# easy_bee_Itsybitsy.net
KiCad netlist of a schematic drawn in EAGLE
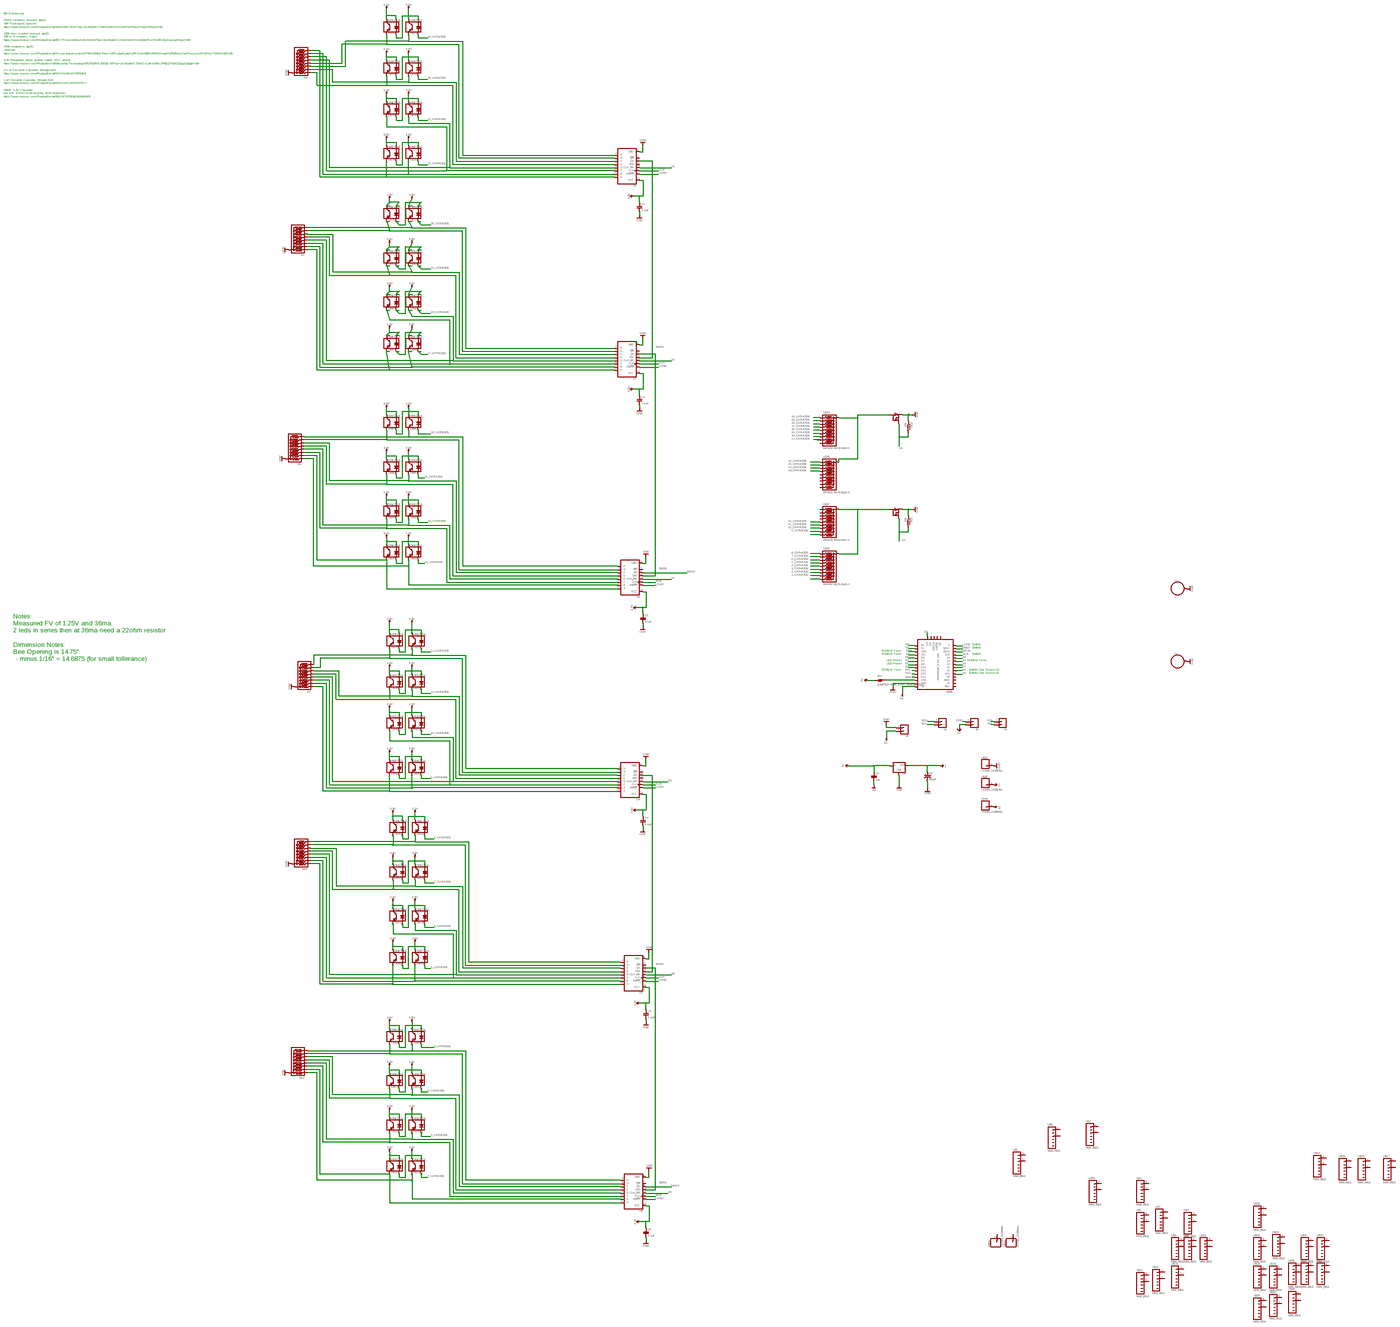
[diagram p0: schematic, sheet 1, overview]
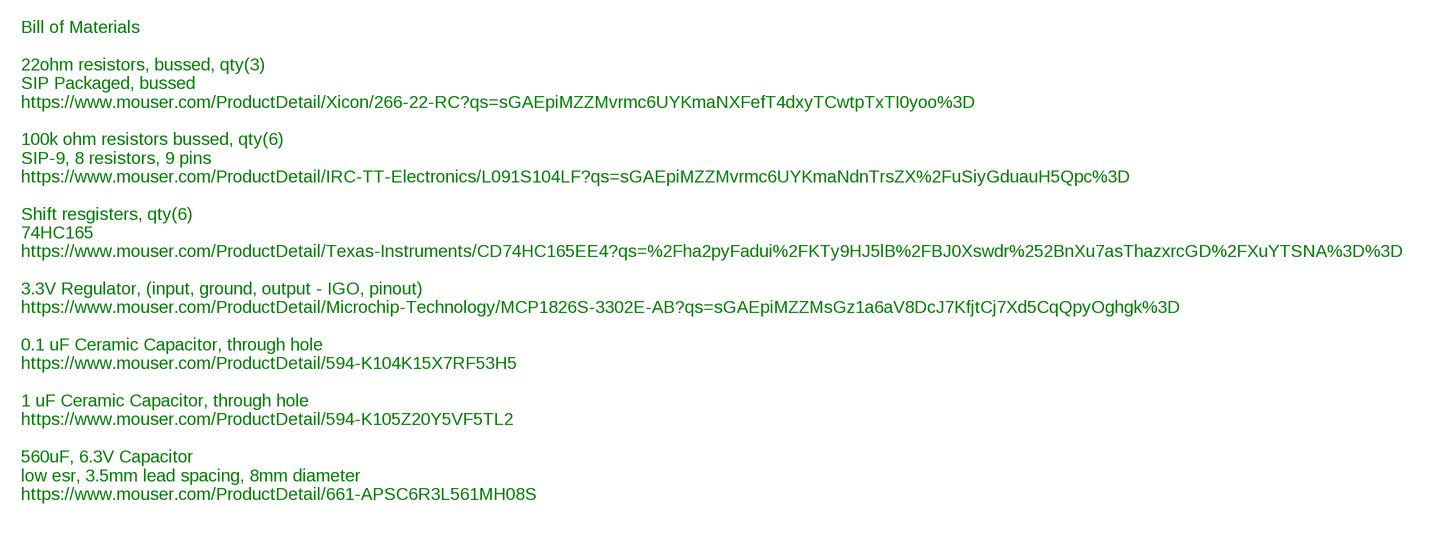
[diagram p1: schematic, sheet 1, part 1 of 5]
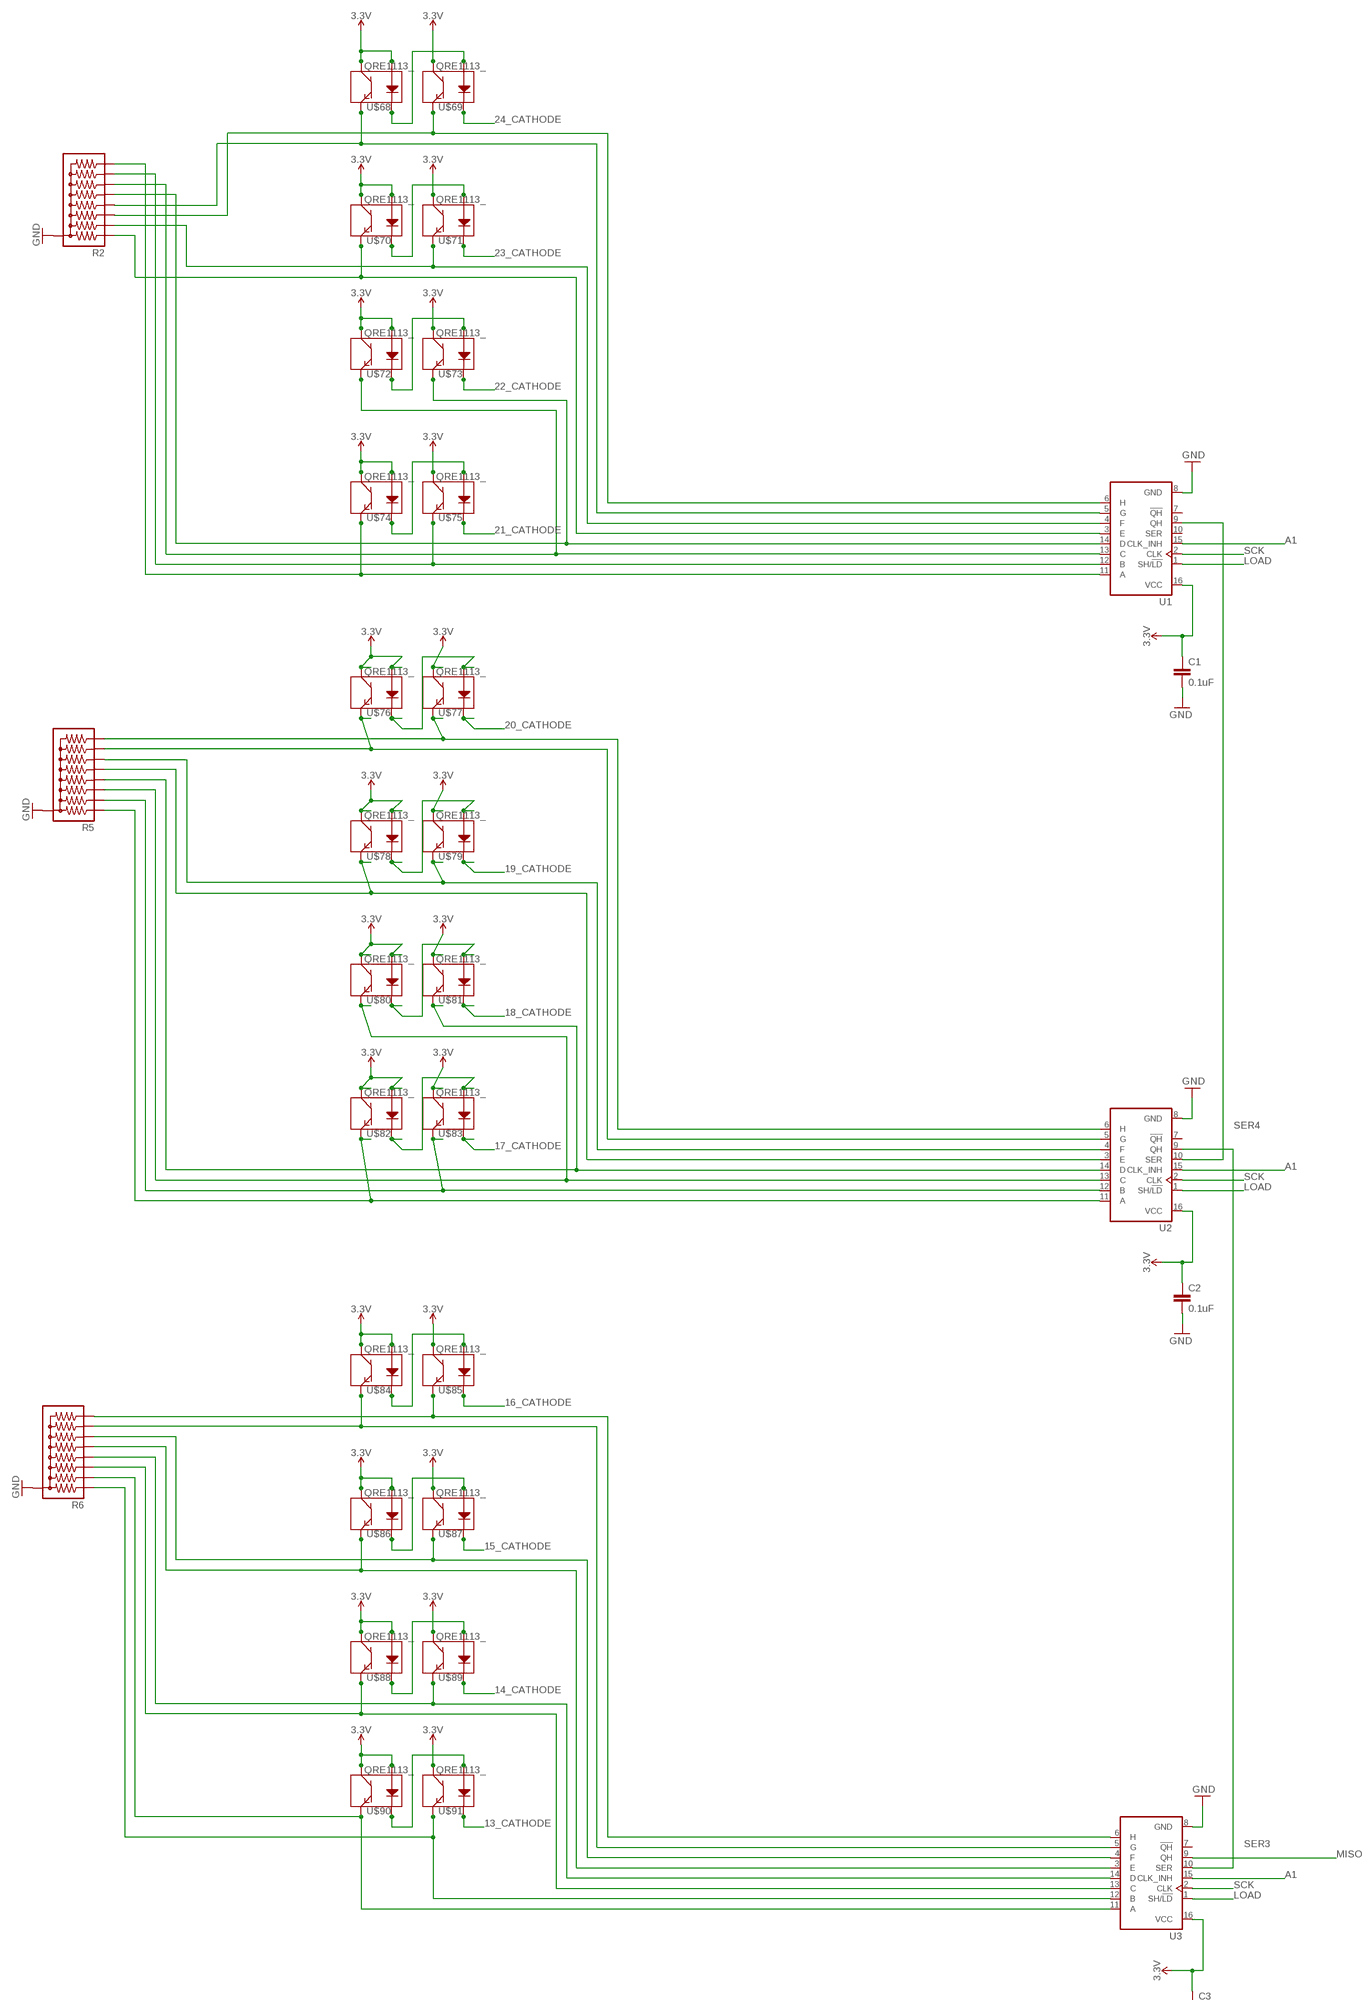
[diagram p2: schematic, sheet 1, part 2 of 5]
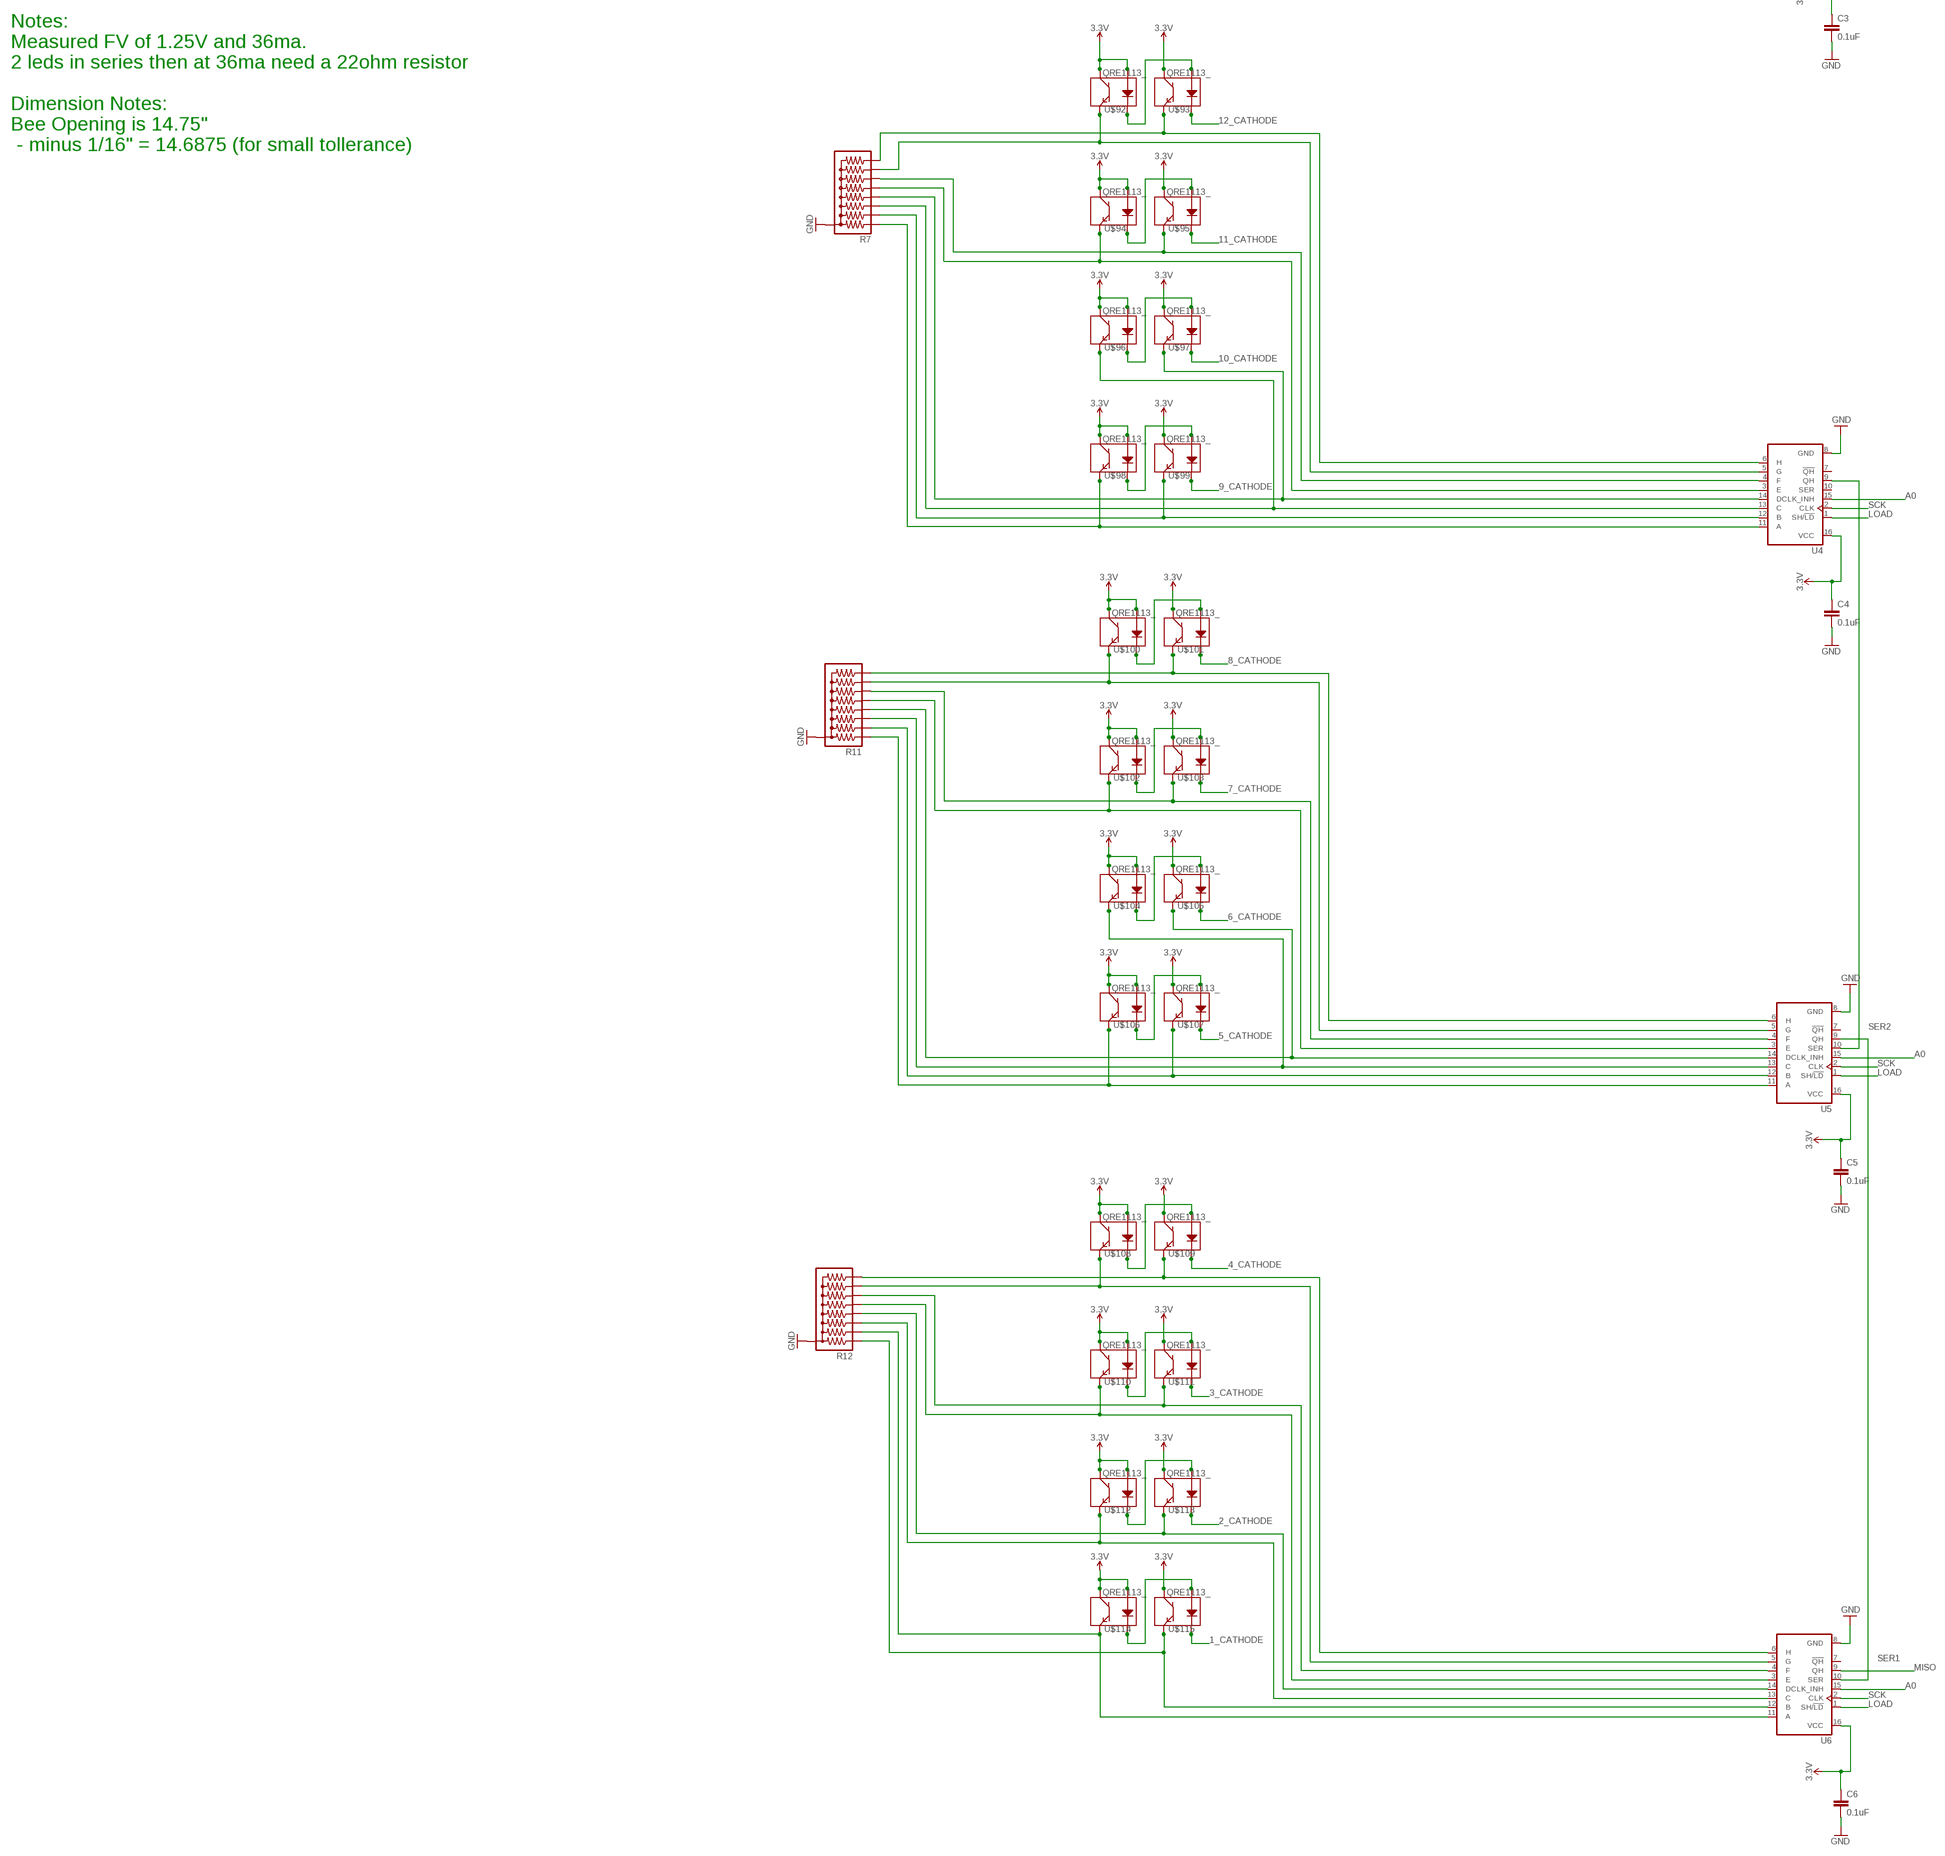
[diagram p3: schematic, sheet 1, part 3 of 5]
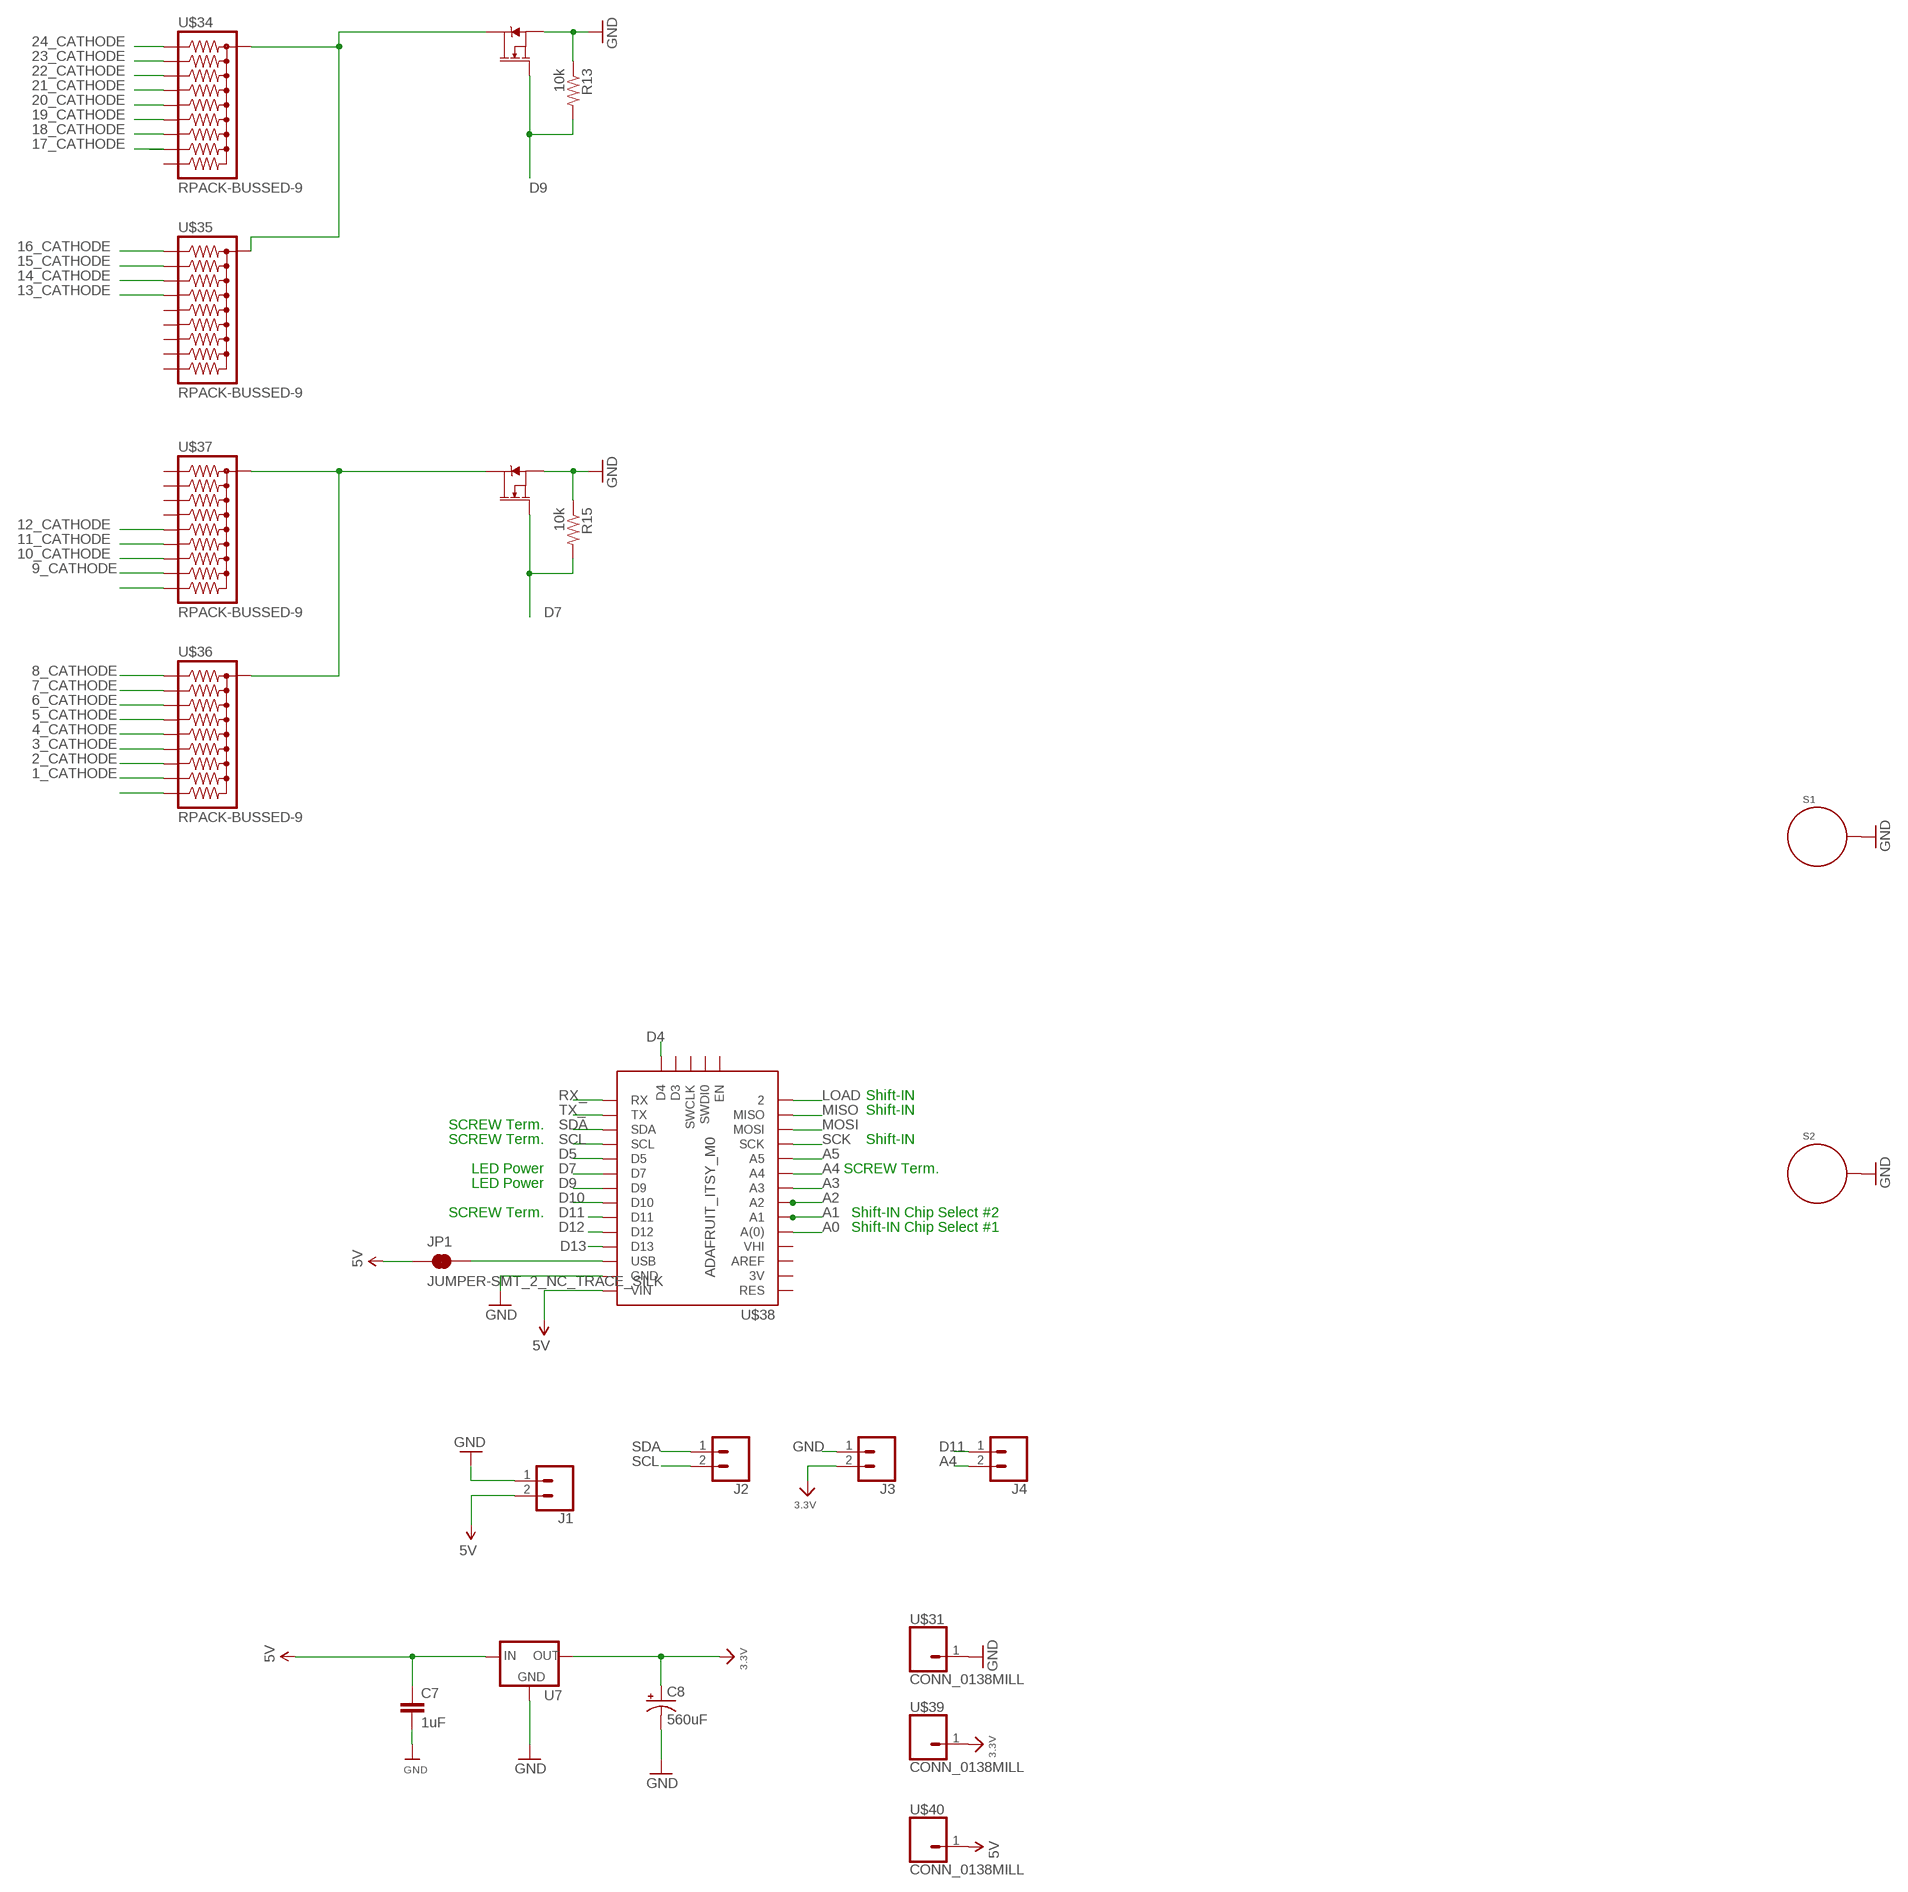
[diagram p4: schematic, sheet 1, part 4 of 5]
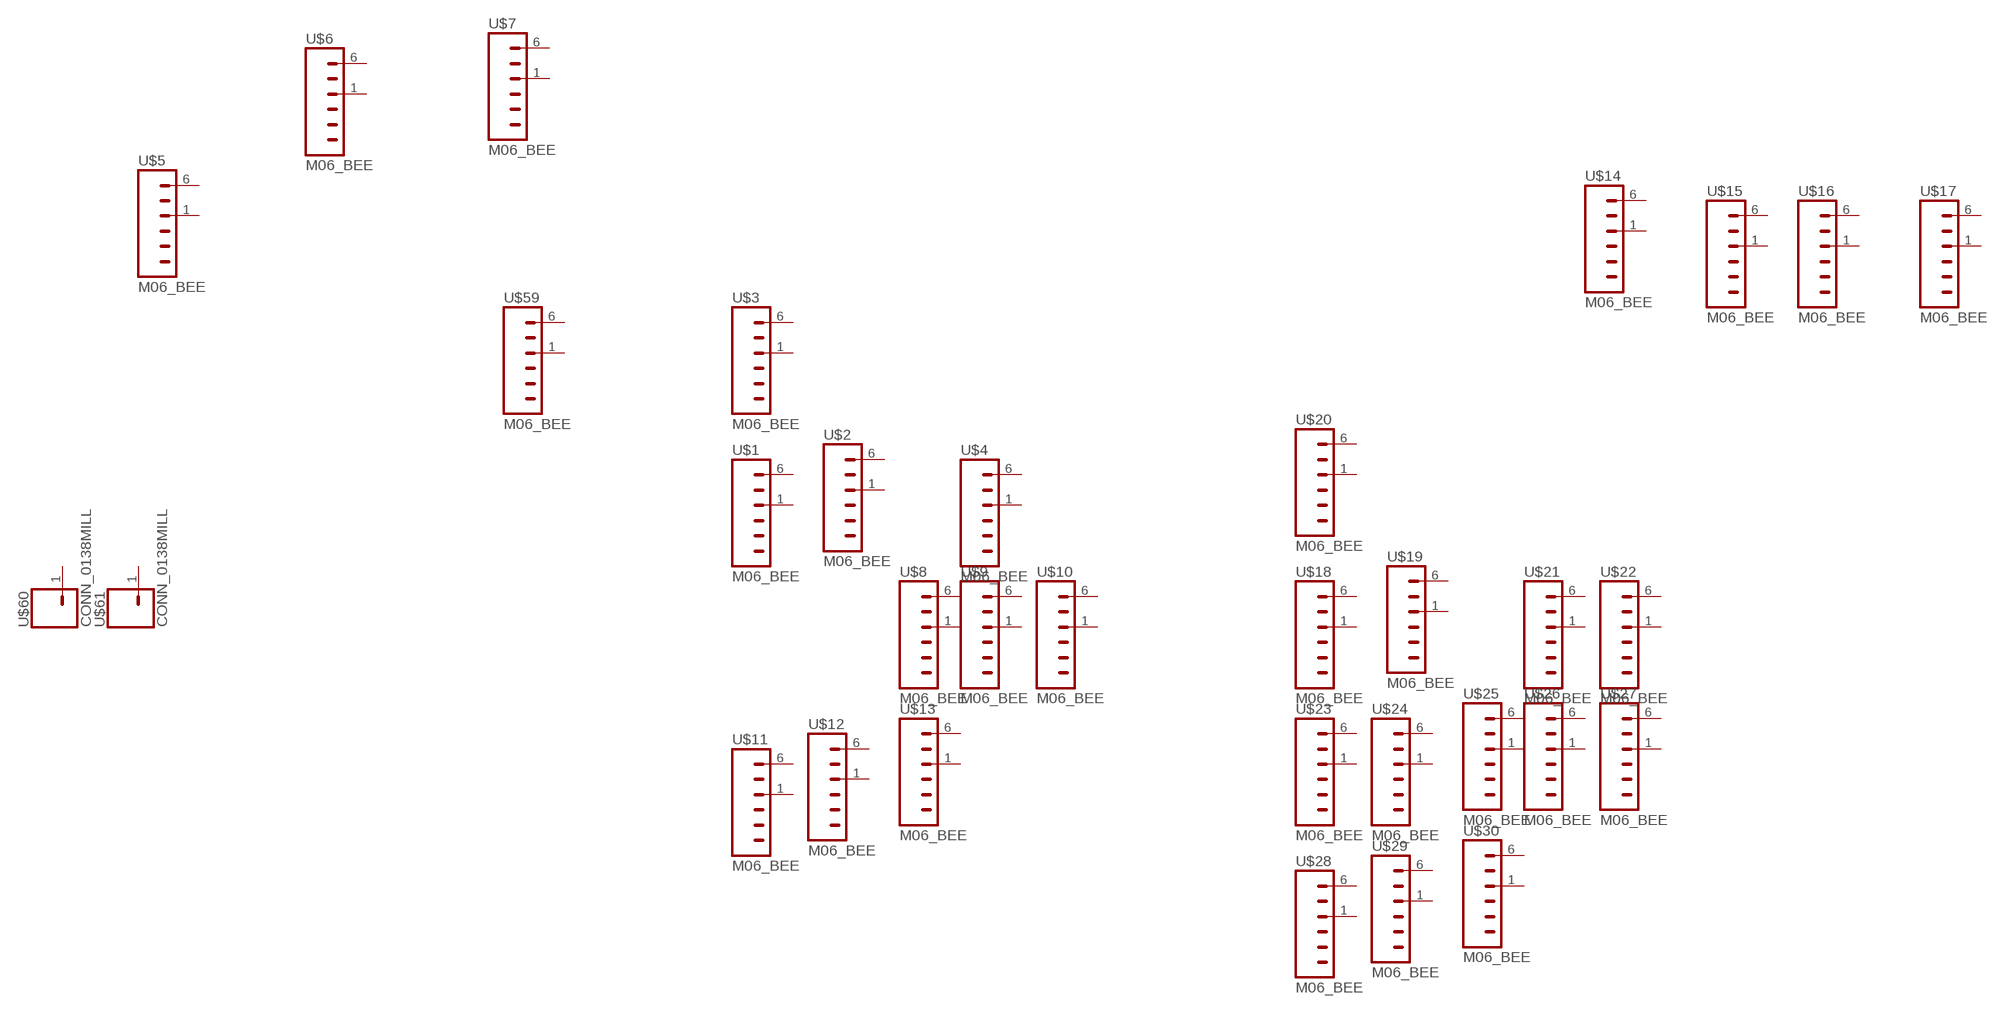
[diagram p5: schematic, sheet 1, part 5 of 5]

(export (version "E")
  (design (tool "Eeschema 10.0.6"))
  (components
    (comp (ref "C1")
      (value "0.1uF")
      (footprint "eagle-import:CAP-PTH-SMALL-KIT")
      (libsource (lib "eagle-import") (part "0.1UF-KIT-EZ-50V-20%"))
    )
    (comp (ref "C2")
      (value "0.1uF")
      (footprint "eagle-import:CAP-PTH-SMALL-KIT")
      (libsource (lib "eagle-import") (part "0.1UF-KIT-EZ-50V-20%"))
    )
    (comp (ref "C3")
      (value "0.1uF")
      (footprint "eagle-import:CAP-PTH-SMALL-KIT")
      (libsource (lib "eagle-import") (part "0.1UF-KIT-EZ-50V-20%"))
    )
    (comp (ref "C4")
      (value "0.1uF")
      (footprint "eagle-import:CAP-PTH-SMALL-KIT")
      (libsource (lib "eagle-import") (part "0.1UF-KIT-EZ-50V-20%"))
    )
    (comp (ref "C5")
      (value "0.1uF")
      (footprint "eagle-import:CAP-PTH-SMALL-KIT")
      (libsource (lib "eagle-import") (part "0.1UF-KIT-EZ-50V-20%"))
    )
    (comp (ref "C6")
      (value "0.1uF")
      (footprint "eagle-import:CAP-PTH-SMALL-KIT")
      (libsource (lib "eagle-import") (part "0.1UF-KIT-EZ-50V-20%"))
    )
    (comp (ref "C7")
      (value "1uF")
      (footprint "eagle-import:CAP-PTH-SMALL-KIT")
      (libsource (lib "eagle-import") (part "0.1UF-KIT-EZ-50V-20%"))
    )
    (comp (ref "C8")
      (value "560uF")
      (footprint "eagle-import:E3,5-8")
      (libsource (lib "eagle-import") (part "CPOL-USE3.5-8"))
    )
    (comp (ref "J1")
      (value "CONN_025MM")
      (footprint "eagle-import:SCREWTERMINAL-5MM-2")
      (libsource (lib "eagle-import") (part "CONN_025MM"))
    )
    (comp (ref "J2")
      (value "CONN_025MM")
      (footprint "eagle-import:SCREWTERMINAL-5MM-2")
      (libsource (lib "eagle-import") (part "CONN_025MM"))
    )
    (comp (ref "J3")
      (value "CONN_025MM")
      (footprint "eagle-import:SCREWTERMINAL-5MM-2")
      (libsource (lib "eagle-import") (part "CONN_025MM"))
    )
    (comp (ref "J4")
      (value "CONN_025MM")
      (footprint "eagle-import:SCREWTERMINAL-5MM-2")
      (libsource (lib "eagle-import") (part "CONN_025MM"))
    )
    (comp (ref "JP1")
      (value "JUMPER-SMT_2_NC_TRACE_SILK")
      (footprint "eagle-import:SMT-JUMPER_2_NC_TRACE_SILK")
      (libsource (lib "eagle-import") (part "JUMPER-SMT_2_NC_TRACE_SILK"))
    )
    (comp (ref "Q6")
      (value "60V/32A/35mΩ")
      (footprint "eagle-import:TO220V")
      (libsource (lib "eagle-import") (part "MOSFET-NCH-FQP30N06L"))
    )
    (comp (ref "Q7")
      (value "60V/32A/35mΩ")
      (footprint "eagle-import:TO220V")
      (libsource (lib "eagle-import") (part "MOSFET-NCH-FQP30N06L"))
    )
    (comp (ref "R2")
      (value "RPACK-BUSSED-8-SIP-PTH-8")
      (footprint "eagle-import:RPACK-SIP-PTH-8")
      (libsource (lib "eagle-import") (part "RPACK-BUSSED-8-SIP-PTH-8"))
    )
    (comp (ref "R5")
      (value "RPACK-BUSSED-8-SIP-PTH-8")
      (footprint "eagle-import:RPACK-SIP-PTH-8")
      (libsource (lib "eagle-import") (part "RPACK-BUSSED-8-SIP-PTH-8"))
    )
    (comp (ref "R6")
      (value "RPACK-BUSSED-8-SIP-PTH-8")
      (footprint "eagle-import:RPACK-SIP-PTH-8")
      (libsource (lib "eagle-import") (part "RPACK-BUSSED-8-SIP-PTH-8"))
    )
    (comp (ref "R7")
      (value "RPACK-BUSSED-8-SIP-PTH-8")
      (footprint "eagle-import:RPACK-SIP-PTH-8")
      (libsource (lib "eagle-import") (part "RPACK-BUSSED-8-SIP-PTH-8"))
    )
    (comp (ref "R11")
      (value "RPACK-BUSSED-8-SIP-PTH-8")
      (footprint "eagle-import:RPACK-SIP-PTH-8")
      (libsource (lib "eagle-import") (part "RPACK-BUSSED-8-SIP-PTH-8"))
    )
    (comp (ref "R12")
      (value "RPACK-BUSSED-8-SIP-PTH-8")
      (footprint "eagle-import:RPACK-SIP-PTH-8")
      (libsource (lib "eagle-import") (part "RPACK-BUSSED-8-SIP-PTH-8"))
    )
    (comp (ref "R13")
      (value "10k")
      (footprint "eagle-import:AXIAL-0.3")
      (libsource (lib "eagle-import") (part "RESISTORAXIAL-0.3"))
    )
    (comp (ref "R15")
      (value "10k")
      (footprint "eagle-import:AXIAL-0.3")
      (libsource (lib "eagle-import") (part "RESISTORAXIAL-0.3"))
    )
    (comp (ref "S1")
      (value "STANDOFF_ELECTRICAL5-32")
      (footprint "eagle-import:STANDOFF_ELECTRICAL_5_32")
      (libsource (lib "eagle-import") (part "STANDOFF_ELECTRICAL5-32"))
    )
    (comp (ref "S2")
      (value "STANDOFF_ELECTRICAL5-32")
      (footprint "eagle-import:STANDOFF_ELECTRICAL_5_32")
      (libsource (lib "eagle-import") (part "STANDOFF_ELECTRICAL5-32"))
    )
    (comp (ref "U$1")
      (value "M06_BEE")
      (footprint "eagle-import:1X06_BEE")
      (libsource (lib "eagle-import") (part "M06_BEE"))
    )
    (comp (ref "U$2")
      (value "M06_BEE")
      (footprint "eagle-import:1X06_BEE")
      (libsource (lib "eagle-import") (part "M06_BEE"))
    )
    (comp (ref "U$3")
      (value "M06_BEE")
      (footprint "eagle-import:1X06_BEE")
      (libsource (lib "eagle-import") (part "M06_BEE"))
    )
    (comp (ref "U$4")
      (value "M06_BEE")
      (footprint "eagle-import:1X06_BEE")
      (libsource (lib "eagle-import") (part "M06_BEE"))
    )
    (comp (ref "U$5")
      (value "M06_BEE")
      (footprint "eagle-import:1X06_BEE")
      (libsource (lib "eagle-import") (part "M06_BEE"))
    )
    (comp (ref "U$6")
      (value "M06_BEE")
      (footprint "eagle-import:1X06_BEE")
      (libsource (lib "eagle-import") (part "M06_BEE"))
    )
    (comp (ref "U$7")
      (value "M06_BEE")
      (footprint "eagle-import:1X06_BEE")
      (libsource (lib "eagle-import") (part "M06_BEE"))
    )
    (comp (ref "U$8")
      (value "M06_BEE")
      (footprint "eagle-import:1X06_BEE")
      (libsource (lib "eagle-import") (part "M06_BEE"))
    )
    (comp (ref "U$9")
      (value "M06_BEE")
      (footprint "eagle-import:1X06_BEE")
      (libsource (lib "eagle-import") (part "M06_BEE"))
    )
    (comp (ref "U$10")
      (value "M06_BEE")
      (footprint "eagle-import:1X06_BEE")
      (libsource (lib "eagle-import") (part "M06_BEE"))
    )
    (comp (ref "U$11")
      (value "M06_BEE")
      (footprint "eagle-import:1X06_BEE")
      (libsource (lib "eagle-import") (part "M06_BEE"))
    )
    (comp (ref "U$12")
      (value "M06_BEE")
      (footprint "eagle-import:1X06_BEE")
      (libsource (lib "eagle-import") (part "M06_BEE"))
    )
    (comp (ref "U$13")
      (value "M06_BEE")
      (footprint "eagle-import:1X06_BEE")
      (libsource (lib "eagle-import") (part "M06_BEE"))
    )
    (comp (ref "U$14")
      (value "M06_BEE")
      (footprint "eagle-import:1X06_BEE")
      (libsource (lib "eagle-import") (part "M06_BEE"))
    )
    (comp (ref "U$15")
      (value "M06_BEE")
      (footprint "eagle-import:1X06_BEE")
      (libsource (lib "eagle-import") (part "M06_BEE"))
    )
    (comp (ref "U$16")
      (value "M06_BEE")
      (footprint "eagle-import:1X06_BEE")
      (libsource (lib "eagle-import") (part "M06_BEE"))
    )
    (comp (ref "U$17")
      (value "M06_BEE")
      (footprint "eagle-import:1X06_BEE")
      (libsource (lib "eagle-import") (part "M06_BEE"))
    )
    (comp (ref "U$18")
      (value "M06_BEE")
      (footprint "eagle-import:1X06_BEE")
      (libsource (lib "eagle-import") (part "M06_BEE"))
    )
    (comp (ref "U$19")
      (value "M06_BEE")
      (footprint "eagle-import:1X06_BEE")
      (libsource (lib "eagle-import") (part "M06_BEE"))
    )
    (comp (ref "U$20")
      (value "M06_BEE")
      (footprint "eagle-import:1X06_BEE")
      (libsource (lib "eagle-import") (part "M06_BEE"))
    )
    (comp (ref "U$21")
      (value "M06_BEE")
      (footprint "eagle-import:1X06_BEE")
      (libsource (lib "eagle-import") (part "M06_BEE"))
    )
    (comp (ref "U$22")
      (value "M06_BEE")
      (footprint "eagle-import:1X06_BEE")
      (libsource (lib "eagle-import") (part "M06_BEE"))
    )
    (comp (ref "U$23")
      (value "M06_BEE")
      (footprint "eagle-import:1X06_BEE")
      (libsource (lib "eagle-import") (part "M06_BEE"))
    )
    (comp (ref "U$24")
      (value "M06_BEE")
      (footprint "eagle-import:1X06_BEE")
      (libsource (lib "eagle-import") (part "M06_BEE"))
    )
    (comp (ref "U$25")
      (value "M06_BEE")
      (footprint "eagle-import:1X06_BEE")
      (libsource (lib "eagle-import") (part "M06_BEE"))
    )
    (comp (ref "U$26")
      (value "M06_BEE")
      (footprint "eagle-import:1X06_BEE")
      (libsource (lib "eagle-import") (part "M06_BEE"))
    )
    (comp (ref "U$27")
      (value "M06_BEE")
      (footprint "eagle-import:1X06_BEE")
      (libsource (lib "eagle-import") (part "M06_BEE"))
    )
    (comp (ref "U$28")
      (value "M06_BEE")
      (footprint "eagle-import:1X06_BEE")
      (libsource (lib "eagle-import") (part "M06_BEE"))
    )
    (comp (ref "U$29")
      (value "M06_BEE")
      (footprint "eagle-import:1X06_BEE")
      (libsource (lib "eagle-import") (part "M06_BEE"))
    )
    (comp (ref "U$30")
      (value "M06_BEE")
      (footprint "eagle-import:1X06_BEE")
      (libsource (lib "eagle-import") (part "M06_BEE"))
    )
    (comp (ref "U$31")
      (value "CONN_0138MILL")
      (footprint "eagle-import:1X01-40MILL")
      (libsource (lib "eagle-import") (part "CONN_0138MILL"))
    )
    (comp (ref "U$34")
      (value "RPACK-BUSSED-9")
      (footprint "eagle-import:RPACK-SIP-PTH-9")
      (libsource (lib "eagle-import") (part "RPACK-BUSSED-9"))
    )
    (comp (ref "U$35")
      (value "RPACK-BUSSED-9")
      (footprint "eagle-import:RPACK-SIP-PTH-9")
      (libsource (lib "eagle-import") (part "RPACK-BUSSED-9"))
    )
    (comp (ref "U$36")
      (value "RPACK-BUSSED-9")
      (footprint "eagle-import:RPACK-SIP-PTH-9")
      (libsource (lib "eagle-import") (part "RPACK-BUSSED-9"))
    )
    (comp (ref "U$37")
      (value "RPACK-BUSSED-9")
      (footprint "eagle-import:RPACK-SIP-PTH-9")
      (libsource (lib "eagle-import") (part "RPACK-BUSSED-9"))
    )
    (comp (ref "U$38")
      (value "ADAFRUIT_ITSY_M0")
      (footprint "eagle-import:ADAFRUIT_ITS_M0")
      (libsource (lib "eagle-import") (part "ADAFRUIT_ITSY_M0"))
    )
    (comp (ref "U$39")
      (value "CONN_0138MILL")
      (footprint "eagle-import:1X01-40MILL")
      (libsource (lib "eagle-import") (part "CONN_0138MILL"))
    )
    (comp (ref "U$40")
      (value "CONN_0138MILL")
      (footprint "eagle-import:1X01-40MILL")
      (libsource (lib "eagle-import") (part "CONN_0138MILL"))
    )
    (comp (ref "U$59")
      (value "M06_BEE")
      (footprint "eagle-import:1X06_BEE")
      (libsource (lib "eagle-import") (part "M06_BEE"))
    )
    (comp (ref "U$60")
      (value "CONN_0138MILL")
      (footprint "eagle-import:1X01-40MILL")
      (libsource (lib "eagle-import") (part "CONN_0138MILL"))
    )
    (comp (ref "U$61")
      (value "CONN_0138MILL")
      (footprint "eagle-import:1X01-40MILL")
      (libsource (lib "eagle-import") (part "CONN_0138MILL"))
    )
    (comp (ref "U$68")
      (value "QRE1113_")
      (footprint "eagle-import:DIP400W50P180L360H200Q4")
      (libsource (lib "eagle-import") (part "QRE1113_"))
    )
    (comp (ref "U$69")
      (value "QRE1113_")
      (footprint "eagle-import:DIP400W50P180L360H200Q4")
      (libsource (lib "eagle-import") (part "QRE1113_"))
    )
    (comp (ref "U$70")
      (value "QRE1113_")
      (footprint "eagle-import:DIP400W50P180L360H200Q4")
      (libsource (lib "eagle-import") (part "QRE1113_"))
    )
    (comp (ref "U$71")
      (value "QRE1113_")
      (footprint "eagle-import:DIP400W50P180L360H200Q4")
      (libsource (lib "eagle-import") (part "QRE1113_"))
    )
    (comp (ref "U$72")
      (value "QRE1113_")
      (footprint "eagle-import:DIP400W50P180L360H200Q4")
      (libsource (lib "eagle-import") (part "QRE1113_"))
    )
    (comp (ref "U$73")
      (value "QRE1113_")
      (footprint "eagle-import:DIP400W50P180L360H200Q4")
      (libsource (lib "eagle-import") (part "QRE1113_"))
    )
    (comp (ref "U$74")
      (value "QRE1113_")
      (footprint "eagle-import:DIP400W50P180L360H200Q4")
      (libsource (lib "eagle-import") (part "QRE1113_"))
    )
    (comp (ref "U$75")
      (value "QRE1113_")
      (footprint "eagle-import:DIP400W50P180L360H200Q4")
      (libsource (lib "eagle-import") (part "QRE1113_"))
    )
    (comp (ref "U$76")
      (value "QRE1113_")
      (footprint "eagle-import:DIP400W50P180L360H200Q4")
      (libsource (lib "eagle-import") (part "QRE1113_"))
    )
    (comp (ref "U$77")
      (value "QRE1113_")
      (footprint "eagle-import:DIP400W50P180L360H200Q4")
      (libsource (lib "eagle-import") (part "QRE1113_"))
    )
    (comp (ref "U$78")
      (value "QRE1113_")
      (footprint "eagle-import:DIP400W50P180L360H200Q4")
      (libsource (lib "eagle-import") (part "QRE1113_"))
    )
    (comp (ref "U$79")
      (value "QRE1113_")
      (footprint "eagle-import:DIP400W50P180L360H200Q4")
      (libsource (lib "eagle-import") (part "QRE1113_"))
    )
    (comp (ref "U$80")
      (value "QRE1113_")
      (footprint "eagle-import:DIP400W50P180L360H200Q4")
      (libsource (lib "eagle-import") (part "QRE1113_"))
    )
    (comp (ref "U$81")
      (value "QRE1113_")
      (footprint "eagle-import:DIP400W50P180L360H200Q4")
      (libsource (lib "eagle-import") (part "QRE1113_"))
    )
    (comp (ref "U$82")
      (value "QRE1113_")
      (footprint "eagle-import:DIP400W50P180L360H200Q4")
      (libsource (lib "eagle-import") (part "QRE1113_"))
    )
    (comp (ref "U$83")
      (value "QRE1113_")
      (footprint "eagle-import:DIP400W50P180L360H200Q4")
      (libsource (lib "eagle-import") (part "QRE1113_"))
    )
    (comp (ref "U$84")
      (value "QRE1113_")
      (footprint "eagle-import:DIP400W50P180L360H200Q4")
      (libsource (lib "eagle-import") (part "QRE1113_"))
    )
    (comp (ref "U$85")
      (value "QRE1113_")
      (footprint "eagle-import:DIP400W50P180L360H200Q4")
      (libsource (lib "eagle-import") (part "QRE1113_"))
    )
    (comp (ref "U$86")
      (value "QRE1113_")
      (footprint "eagle-import:DIP400W50P180L360H200Q4")
      (libsource (lib "eagle-import") (part "QRE1113_"))
    )
    (comp (ref "U$87")
      (value "QRE1113_")
      (footprint "eagle-import:DIP400W50P180L360H200Q4")
      (libsource (lib "eagle-import") (part "QRE1113_"))
    )
    (comp (ref "U$88")
      (value "QRE1113_")
      (footprint "eagle-import:DIP400W50P180L360H200Q4")
      (libsource (lib "eagle-import") (part "QRE1113_"))
    )
    (comp (ref "U$89")
      (value "QRE1113_")
      (footprint "eagle-import:DIP400W50P180L360H200Q4")
      (libsource (lib "eagle-import") (part "QRE1113_"))
    )
    (comp (ref "U$90")
      (value "QRE1113_")
      (footprint "eagle-import:DIP400W50P180L360H200Q4")
      (libsource (lib "eagle-import") (part "QRE1113_"))
    )
    (comp (ref "U$91")
      (value "QRE1113_")
      (footprint "eagle-import:DIP400W50P180L360H200Q4")
      (libsource (lib "eagle-import") (part "QRE1113_"))
    )
    (comp (ref "U$92")
      (value "QRE1113_")
      (footprint "eagle-import:DIP400W50P180L360H200Q4")
      (libsource (lib "eagle-import") (part "QRE1113_"))
    )
    (comp (ref "U$93")
      (value "QRE1113_")
      (footprint "eagle-import:DIP400W50P180L360H200Q4")
      (libsource (lib "eagle-import") (part "QRE1113_"))
    )
    (comp (ref "U$94")
      (value "QRE1113_")
      (footprint "eagle-import:DIP400W50P180L360H200Q4")
      (libsource (lib "eagle-import") (part "QRE1113_"))
    )
    (comp (ref "U$95")
      (value "QRE1113_")
      (footprint "eagle-import:DIP400W50P180L360H200Q4")
      (libsource (lib "eagle-import") (part "QRE1113_"))
    )
    (comp (ref "U$96")
      (value "QRE1113_")
      (footprint "eagle-import:DIP400W50P180L360H200Q4")
      (libsource (lib "eagle-import") (part "QRE1113_"))
    )
    (comp (ref "U$97")
      (value "QRE1113_")
      (footprint "eagle-import:DIP400W50P180L360H200Q4")
      (libsource (lib "eagle-import") (part "QRE1113_"))
    )
    (comp (ref "U$98")
      (value "QRE1113_")
      (footprint "eagle-import:DIP400W50P180L360H200Q4")
      (libsource (lib "eagle-import") (part "QRE1113_"))
    )
    (comp (ref "U$99")
      (value "QRE1113_")
      (footprint "eagle-import:DIP400W50P180L360H200Q4")
      (libsource (lib "eagle-import") (part "QRE1113_"))
    )
    (comp (ref "U$100")
      (value "QRE1113_")
      (footprint "eagle-import:DIP400W50P180L360H200Q4")
      (libsource (lib "eagle-import") (part "QRE1113_"))
    )
    (comp (ref "U$101")
      (value "QRE1113_")
      (footprint "eagle-import:DIP400W50P180L360H200Q4")
      (libsource (lib "eagle-import") (part "QRE1113_"))
    )
    (comp (ref "U$102")
      (value "QRE1113_")
      (footprint "eagle-import:DIP400W50P180L360H200Q4")
      (libsource (lib "eagle-import") (part "QRE1113_"))
    )
    (comp (ref "U$103")
      (value "QRE1113_")
      (footprint "eagle-import:DIP400W50P180L360H200Q4")
      (libsource (lib "eagle-import") (part "QRE1113_"))
    )
    (comp (ref "U$104")
      (value "QRE1113_")
      (footprint "eagle-import:DIP400W50P180L360H200Q4")
      (libsource (lib "eagle-import") (part "QRE1113_"))
    )
    (comp (ref "U$105")
      (value "QRE1113_")
      (footprint "eagle-import:DIP400W50P180L360H200Q4")
      (libsource (lib "eagle-import") (part "QRE1113_"))
    )
    (comp (ref "U$106")
      (value "QRE1113_")
      (footprint "eagle-import:DIP400W50P180L360H200Q4")
      (libsource (lib "eagle-import") (part "QRE1113_"))
    )
    (comp (ref "U$107")
      (value "QRE1113_")
      (footprint "eagle-import:DIP400W50P180L360H200Q4")
      (libsource (lib "eagle-import") (part "QRE1113_"))
    )
    (comp (ref "U$108")
      (value "QRE1113_")
      (footprint "eagle-import:DIP400W50P180L360H200Q4")
      (libsource (lib "eagle-import") (part "QRE1113_"))
    )
    (comp (ref "U$109")
      (value "QRE1113_")
      (footprint "eagle-import:DIP400W50P180L360H200Q4")
      (libsource (lib "eagle-import") (part "QRE1113_"))
    )
    (comp (ref "U$110")
      (value "QRE1113_")
      (footprint "eagle-import:DIP400W50P180L360H200Q4")
      (libsource (lib "eagle-import") (part "QRE1113_"))
    )
    (comp (ref "U$111")
      (value "QRE1113_")
      (footprint "eagle-import:DIP400W50P180L360H200Q4")
      (libsource (lib "eagle-import") (part "QRE1113_"))
    )
    (comp (ref "U$112")
      (value "QRE1113_")
      (footprint "eagle-import:DIP400W50P180L360H200Q4")
      (libsource (lib "eagle-import") (part "QRE1113_"))
    )
    (comp (ref "U$113")
      (value "QRE1113_")
      (footprint "eagle-import:DIP400W50P180L360H200Q4")
      (libsource (lib "eagle-import") (part "QRE1113_"))
    )
    (comp (ref "U$114")
      (value "QRE1113_")
      (footprint "eagle-import:DIP400W50P180L360H200Q4")
      (libsource (lib "eagle-import") (part "QRE1113_"))
    )
    (comp (ref "U$115")
      (value "QRE1113_")
      (footprint "eagle-import:DIP400W50P180L360H200Q4")
      (libsource (lib "eagle-import") (part "QRE1113_"))
    )
    (comp (ref "U1")
      (value "74165")
      (footprint "eagle-import:DIP16")
      (libsource (lib "eagle-import") (part "74165"))
    )
    (comp (ref "U2")
      (value "74165")
      (footprint "eagle-import:DIP16")
      (libsource (lib "eagle-import") (part "74165"))
    )
    (comp (ref "U3")
      (value "74165")
      (footprint "eagle-import:DIP16")
      (libsource (lib "eagle-import") (part "74165"))
    )
    (comp (ref "U4")
      (value "74165")
      (footprint "eagle-import:DIP16")
      (libsource (lib "eagle-import") (part "74165"))
    )
    (comp (ref "U5")
      (value "74165")
      (footprint "eagle-import:DIP16")
      (libsource (lib "eagle-import") (part "74165"))
    )
    (comp (ref "U6")
      (value "74165")
      (footprint "eagle-import:DIP16")
      (libsource (lib "eagle-import") (part "74165"))
    )
    (comp (ref "U7")
      (value "V_REG_78XXSINK")
      (footprint "eagle-import:TO220-IGO")
      (libsource (lib "eagle-import") (part "V_REG_78XXSINK"))
    )
  )
  (nets
    (net (code "1") (name "/1_CATHODE") (class "Default")
      (node (ref "U$115") (pin "2") (pinfunction "K_2") (pintype "bidirectional"))
      (node (ref "U$36") (pin "P$9") (pinfunction "9_P$9") (pintype "passive"))
    )
    (net (code "2") (name "/2_CATHODE") (class "Default")
      (node (ref "U$113") (pin "2") (pinfunction "K_2") (pintype "bidirectional"))
      (node (ref "U$36") (pin "P$8") (pinfunction "8_P$8") (pintype "passive"))
    )
    (net (code "3") (name "/3_CATHODE") (class "Default")
      (node (ref "U$111") (pin "2") (pinfunction "K_2") (pintype "bidirectional"))
      (node (ref "U$36") (pin "P$7") (pinfunction "7_P$7") (pintype "passive"))
    )
    (net (code "4") (name "/4_CATHODE") (class "Default")
      (node (ref "U$109") (pin "2") (pinfunction "K_2") (pintype "bidirectional"))
      (node (ref "U$36") (pin "P$6") (pinfunction "6_P$6") (pintype "passive"))
    )
    (net (code "5") (name "/5_CATHODE") (class "Default")
      (node (ref "U$107") (pin "2") (pinfunction "K_2") (pintype "bidirectional"))
      (node (ref "U$36") (pin "P$5") (pinfunction "5_P$5") (pintype "passive"))
    )
    (net (code "6") (name "/6_CATHODE") (class "Default")
      (node (ref "U$105") (pin "2") (pinfunction "K_2") (pintype "bidirectional"))
      (node (ref "U$36") (pin "P$4") (pinfunction "4_P$4") (pintype "passive"))
    )
    (net (code "7") (name "/7_CATHODE") (class "Default")
      (node (ref "U$103") (pin "2") (pinfunction "K_2") (pintype "bidirectional"))
      (node (ref "U$36") (pin "P$3") (pinfunction "3_P$3") (pintype "passive"))
    )
    (net (code "8") (name "/8_CATHODE") (class "Default")
      (node (ref "U$101") (pin "2") (pinfunction "K_2") (pintype "bidirectional"))
      (node (ref "U$36") (pin "P$2") (pinfunction "2_P$2") (pintype "passive"))
    )
    (net (code "9") (name "/9_CATHODE") (class "Default")
      (node (ref "U$37") (pin "P$9") (pinfunction "9_P$9") (pintype "passive"))
      (node (ref "U$99") (pin "2") (pinfunction "K_2") (pintype "bidirectional"))
    )
    (net (code "10") (name "/10_CATHODE") (class "Default")
      (node (ref "U$37") (pin "P$8") (pinfunction "8_P$8") (pintype "passive"))
      (node (ref "U$97") (pin "2") (pinfunction "K_2") (pintype "bidirectional"))
    )
    (net (code "11") (name "/11_CATHODE") (class "Default")
      (node (ref "U$37") (pin "P$7") (pinfunction "7_P$7") (pintype "passive"))
      (node (ref "U$95") (pin "2") (pinfunction "K_2") (pintype "bidirectional"))
    )
    (net (code "12") (name "/12_CATHODE") (class "Default")
      (node (ref "U$37") (pin "P$6") (pinfunction "6_P$6") (pintype "passive"))
      (node (ref "U$93") (pin "2") (pinfunction "K_2") (pintype "bidirectional"))
    )
    (net (code "13") (name "/13_CATHODE") (class "Default")
      (node (ref "U$35") (pin "P$5") (pinfunction "5_P$5") (pintype "passive"))
      (node (ref "U$91") (pin "2") (pinfunction "K_2") (pintype "bidirectional"))
    )
    (net (code "14") (name "/14_CATHODE") (class "Default")
      (node (ref "U$35") (pin "P$4") (pinfunction "4_P$4") (pintype "passive"))
      (node (ref "U$89") (pin "2") (pinfunction "K_2") (pintype "bidirectional"))
    )
    (net (code "15") (name "/15_CATHODE") (class "Default")
      (node (ref "U$35") (pin "P$3") (pinfunction "3_P$3") (pintype "passive"))
      (node (ref "U$87") (pin "2") (pinfunction "K_2") (pintype "bidirectional"))
    )
    (net (code "16") (name "/16_CATHODE") (class "Default")
      (node (ref "U$35") (pin "P$2") (pinfunction "2_P$2") (pintype "passive"))
      (node (ref "U$85") (pin "2") (pinfunction "K_2") (pintype "bidirectional"))
    )
    (net (code "17") (name "/17_CATHODE") (class "Default")
      (node (ref "U$34") (pin "P$9") (pinfunction "9_P$9") (pintype "passive"))
      (node (ref "U$83") (pin "2") (pinfunction "K_2") (pintype "bidirectional"))
    )
    (net (code "18") (name "/18_CATHODE") (class "Default")
      (node (ref "U$34") (pin "P$8") (pinfunction "8_P$8") (pintype "passive"))
      (node (ref "U$81") (pin "2") (pinfunction "K_2") (pintype "bidirectional"))
    )
    (net (code "19") (name "/19_CATHODE") (class "Default")
      (node (ref "U$34") (pin "P$7") (pinfunction "7_P$7") (pintype "passive"))
      (node (ref "U$79") (pin "2") (pinfunction "K_2") (pintype "bidirectional"))
    )
    (net (code "20") (name "/20_CATHODE") (class "Default")
      (node (ref "U$34") (pin "P$6") (pinfunction "6_P$6") (pintype "passive"))
      (node (ref "U$77") (pin "2") (pinfunction "K_2") (pintype "bidirectional"))
    )
    (net (code "21") (name "/21_CATHODE") (class "Default")
      (node (ref "U$34") (pin "P$5") (pinfunction "5_P$5") (pintype "passive"))
      (node (ref "U$75") (pin "2") (pinfunction "K_2") (pintype "bidirectional"))
    )
    (net (code "22") (name "/22_CATHODE") (class "Default")
      (node (ref "U$34") (pin "P$4") (pinfunction "4_P$4") (pintype "passive"))
      (node (ref "U$73") (pin "2") (pinfunction "K_2") (pintype "bidirectional"))
    )
    (net (code "23") (name "/23_CATHODE") (class "Default")
      (node (ref "U$34") (pin "P$3") (pinfunction "3_P$3") (pintype "passive"))
      (node (ref "U$71") (pin "2") (pinfunction "K_2") (pintype "bidirectional"))
    )
    (net (code "24") (name "/24_CATHODE") (class "Default")
      (node (ref "U$34") (pin "P$2") (pinfunction "2_P$2") (pintype "passive"))
      (node (ref "U$69") (pin "2") (pinfunction "K_2") (pintype "bidirectional"))
    )
    (net (code "25") (name "/A0") (class "Default")
      (node (ref "U$38") (pin "A0") (pinfunction "A(0)_A0") (pintype "bidirectional"))
      (node (ref "U4") (pin "15") (pinfunction "CLK_INH_15") (pintype "input"))
      (node (ref "U5") (pin "15") (pinfunction "CLK_INH_15") (pintype "input"))
      (node (ref "U6") (pin "15") (pinfunction "CLK_INH_15") (pintype "input"))
    )
    (net (code "26") (name "/A1") (class "Default")
      (node (ref "U$38") (pin "A1") (pinfunction "A1_A1") (pintype "bidirectional"))
      (node (ref "U1") (pin "15") (pinfunction "CLK_INH_15") (pintype "input"))
      (node (ref "U2") (pin "15") (pinfunction "CLK_INH_15") (pintype "input"))
      (node (ref "U3") (pin "15") (pinfunction "CLK_INH_15") (pintype "input"))
    )
    (net (code "27") (name "/A2") (class "Default")
      (node (ref "U$38") (pin "A2") (pinfunction "A2_A2") (pintype "bidirectional"))
    )
    (net (code "28") (name "/A3") (class "Default")
      (node (ref "U$38") (pin "A3") (pinfunction "A3_A3") (pintype "bidirectional"))
    )
    (net (code "29") (name "/A4") (class "Default")
      (node (ref "J4") (pin "2") (pinfunction "2_2") (pintype "passive"))
      (node (ref "U$38") (pin "A4") (pinfunction "A4_A4") (pintype "bidirectional"))
    )
    (net (code "30") (name "/A5") (class "Default")
      (node (ref "U$38") (pin "A5") (pinfunction "A5_A5") (pintype "bidirectional"))
    )
    (net (code "31") (name "/D4") (class "Default")
      (node (ref "U$38") (pin "D4") (pinfunction "D4_D4") (pintype "bidirectional"))
    )
    (net (code "32") (name "/D5") (class "Default")
      (node (ref "U$38") (pin "D5") (pinfunction "D5_D5") (pintype "bidirectional"))
    )
    (net (code "33") (name "/D7") (class "Default")
      (node (ref "Q7") (pin "1") (pinfunction "G_1") (pintype "bidirectional"))
      (node (ref "R15") (pin "P$2") (pinfunction "2_P$2") (pintype "passive"))
      (node (ref "U$38") (pin "D7") (pinfunction "D7_D7") (pintype "bidirectional"))
    )
    (net (code "34") (name "/D9") (class "Default")
      (node (ref "Q6") (pin "1") (pinfunction "G_1") (pintype "bidirectional"))
      (node (ref "R13") (pin "P$2") (pinfunction "2_P$2") (pintype "passive"))
      (node (ref "U$38") (pin "D9") (pinfunction "D9_D9") (pintype "bidirectional"))
    )
    (net (code "35") (name "/D10") (class "Default")
      (node (ref "U$38") (pin "D10") (pinfunction "D10_D10") (pintype "bidirectional"))
    )
    (net (code "36") (name "/D11") (class "Default")
      (node (ref "J4") (pin "1") (pinfunction "1_1") (pintype "passive"))
      (node (ref "U$38") (pin "D11") (pinfunction "D11_D11") (pintype "bidirectional"))
    )
    (net (code "37") (name "/D12") (class "Default")
      (node (ref "U$38") (pin "D12") (pinfunction "D12_D12") (pintype "bidirectional"))
    )
    (net (code "38") (name "/D13") (class "Default")
      (node (ref "U$38") (pin "D13") (pinfunction "D13_D13") (pintype "bidirectional"))
    )
    (net (code "39") (name "/LOAD") (class "Default")
      (node (ref "U$38") (pin "2") (pinfunction "2_2") (pintype "bidirectional"))
      (node (ref "U1") (pin "1") (pinfunction "SH/~{LD}_1") (pintype "input"))
      (node (ref "U2") (pin "1") (pinfunction "SH/~{LD}_1") (pintype "input"))
      (node (ref "U3") (pin "1") (pinfunction "SH/~{LD}_1") (pintype "input"))
      (node (ref "U4") (pin "1") (pinfunction "SH/~{LD}_1") (pintype "input"))
      (node (ref "U5") (pin "1") (pinfunction "SH/~{LD}_1") (pintype "input"))
      (node (ref "U6") (pin "1") (pinfunction "SH/~{LD}_1") (pintype "input"))
    )
    (net (code "40") (name "/MISO") (class "Default")
      (node (ref "U$38") (pin "MISO") (pinfunction "MISO_MISO") (pintype "bidirectional"))
      (node (ref "U3") (pin "9") (pinfunction "QH_9") (pintype "tri_state"))
      (node (ref "U6") (pin "9") (pinfunction "QH_9") (pintype "tri_state"))
    )
    (net (code "41") (name "/MOSI") (class "Default")
      (node (ref "U$38") (pin "MOSI") (pinfunction "MOSI_MOSI") (pintype "bidirectional"))
    )
    (net (code "42") (name "/RX_") (class "Default")
      (node (ref "U$38") (pin "RX") (pinfunction "RX_RX") (pintype "bidirectional"))
    )
    (net (code "43") (name "/SCK") (class "Default")
      (node (ref "U$38") (pin "SCK") (pinfunction "SCK_SCK") (pintype "bidirectional"))
      (node (ref "U1") (pin "2") (pinfunction "CLK_2") (pintype "input"))
      (node (ref "U2") (pin "2") (pinfunction "CLK_2") (pintype "input"))
      (node (ref "U3") (pin "2") (pinfunction "CLK_2") (pintype "input"))
      (node (ref "U4") (pin "2") (pinfunction "CLK_2") (pintype "input"))
      (node (ref "U5") (pin "2") (pinfunction "CLK_2") (pintype "input"))
      (node (ref "U6") (pin "2") (pinfunction "CLK_2") (pintype "input"))
    )
    (net (code "44") (name "/SCL") (class "Default")
      (node (ref "J2") (pin "2") (pinfunction "2_2") (pintype "passive"))
      (node (ref "U$38") (pin "SCL") (pinfunction "SCL_SCL") (pintype "bidirectional"))
    )
    (net (code "45") (name "/SDA") (class "Default")
      (node (ref "J2") (pin "1") (pinfunction "1_1") (pintype "passive"))
      (node (ref "U$38") (pin "SDA") (pinfunction "SDA_SDA") (pintype "bidirectional"))
    )
    (net (code "46") (name "/SER1") (class "Default")
      (node (ref "U5") (pin "9") (pinfunction "QH_9") (pintype "tri_state"))
      (node (ref "U6") (pin "10") (pinfunction "SER_10") (pintype "input"))
    )
    (net (code "47") (name "/SER2") (class "Default")
      (node (ref "U4") (pin "9") (pinfunction "QH_9") (pintype "tri_state"))
      (node (ref "U5") (pin "10") (pinfunction "SER_10") (pintype "input"))
    )
    (net (code "48") (name "/SER3") (class "Default")
      (node (ref "U2") (pin "9") (pinfunction "QH_9") (pintype "tri_state"))
      (node (ref "U3") (pin "10") (pinfunction "SER_10") (pintype "input"))
    )
    (net (code "49") (name "/SER4") (class "Default")
      (node (ref "U1") (pin "9") (pinfunction "QH_9") (pintype "tri_state"))
      (node (ref "U2") (pin "10") (pinfunction "SER_10") (pintype "input"))
    )
    (net (code "50") (name "/TX_") (class "Default")
      (node (ref "U$38") (pin "TX") (pinfunction "TX_TX") (pintype "bidirectional"))
    )
    (net (code "51") (name "3.3V") (class "Default")
      (node (ref "C1") (pin "1") (pinfunction "1_1") (pintype "passive"))
      (node (ref "C2") (pin "1") (pinfunction "1_1") (pintype "passive"))
      (node (ref "C3") (pin "1") (pinfunction "1_1") (pintype "passive"))
      (node (ref "C4") (pin "1") (pinfunction "1_1") (pintype "passive"))
      (node (ref "C5") (pin "1") (pinfunction "1_1") (pintype "passive"))
      (node (ref "C6") (pin "1") (pinfunction "1_1") (pintype "passive"))
      (node (ref "C8") (pin "+") (pinfunction "+_+") (pintype "passive"))
      (node (ref "J3") (pin "2") (pinfunction "2_2") (pintype "passive"))
      (node (ref "U$100") (pin "1") (pinfunction "A_1") (pintype "bidirectional"))
      (node (ref "U$100") (pin "3") (pinfunction "C_3") (pintype "bidirectional"))
      (node (ref "U$101") (pin "3") (pinfunction "C_3") (pintype "bidirectional"))
      (node (ref "U$102") (pin "1") (pinfunction "A_1") (pintype "bidirectional"))
      (node (ref "U$102") (pin "3") (pinfunction "C_3") (pintype "bidirectional"))
      (node (ref "U$103") (pin "3") (pinfunction "C_3") (pintype "bidirectional"))
      (node (ref "U$104") (pin "1") (pinfunction "A_1") (pintype "bidirectional"))
      (node (ref "U$104") (pin "3") (pinfunction "C_3") (pintype "bidirectional"))
      (node (ref "U$105") (pin "3") (pinfunction "C_3") (pintype "bidirectional"))
      (node (ref "U$106") (pin "1") (pinfunction "A_1") (pintype "bidirectional"))
      (node (ref "U$106") (pin "3") (pinfunction "C_3") (pintype "bidirectional"))
      (node (ref "U$107") (pin "3") (pinfunction "C_3") (pintype "bidirectional"))
      (node (ref "U$108") (pin "1") (pinfunction "A_1") (pintype "bidirectional"))
      (node (ref "U$108") (pin "3") (pinfunction "C_3") (pintype "bidirectional"))
      (node (ref "U$109") (pin "3") (pinfunction "C_3") (pintype "bidirectional"))
      (node (ref "U$110") (pin "1") (pinfunction "A_1") (pintype "bidirectional"))
      (node (ref "U$110") (pin "3") (pinfunction "C_3") (pintype "bidirectional"))
      (node (ref "U$111") (pin "3") (pinfunction "C_3") (pintype "bidirectional"))
      (node (ref "U$112") (pin "1") (pinfunction "A_1") (pintype "bidirectional"))
      (node (ref "U$112") (pin "3") (pinfunction "C_3") (pintype "bidirectional"))
      (node (ref "U$113") (pin "3") (pinfunction "C_3") (pintype "bidirectional"))
      (node (ref "U$114") (pin "1") (pinfunction "A_1") (pintype "bidirectional"))
      (node (ref "U$114") (pin "3") (pinfunction "C_3") (pintype "bidirectional"))
      (node (ref "U$115") (pin "3") (pinfunction "C_3") (pintype "bidirectional"))
      (node (ref "U$39") (pin "1") (pinfunction "1_1") (pintype "passive"))
      (node (ref "U$68") (pin "1") (pinfunction "A_1") (pintype "bidirectional"))
      (node (ref "U$68") (pin "3") (pinfunction "C_3") (pintype "bidirectional"))
      (node (ref "U$69") (pin "3") (pinfunction "C_3") (pintype "bidirectional"))
      (node (ref "U$70") (pin "1") (pinfunction "A_1") (pintype "bidirectional"))
      (node (ref "U$70") (pin "3") (pinfunction "C_3") (pintype "bidirectional"))
      (node (ref "U$71") (pin "3") (pinfunction "C_3") (pintype "bidirectional"))
      (node (ref "U$72") (pin "1") (pinfunction "A_1") (pintype "bidirectional"))
      (node (ref "U$72") (pin "3") (pinfunction "C_3") (pintype "bidirectional"))
      (node (ref "U$73") (pin "3") (pinfunction "C_3") (pintype "bidirectional"))
      (node (ref "U$74") (pin "1") (pinfunction "A_1") (pintype "bidirectional"))
      (node (ref "U$74") (pin "3") (pinfunction "C_3") (pintype "bidirectional"))
      (node (ref "U$75") (pin "3") (pinfunction "C_3") (pintype "bidirectional"))
      (node (ref "U$76") (pin "1") (pinfunction "A_1") (pintype "bidirectional"))
      (node (ref "U$76") (pin "3") (pinfunction "C_3") (pintype "bidirectional"))
      (node (ref "U$77") (pin "3") (pinfunction "C_3") (pintype "bidirectional"))
      (node (ref "U$78") (pin "1") (pinfunction "A_1") (pintype "bidirectional"))
      (node (ref "U$78") (pin "3") (pinfunction "C_3") (pintype "bidirectional"))
      (node (ref "U$79") (pin "3") (pinfunction "C_3") (pintype "bidirectional"))
      (node (ref "U$80") (pin "1") (pinfunction "A_1") (pintype "bidirectional"))
      (node (ref "U$80") (pin "3") (pinfunction "C_3") (pintype "bidirectional"))
      (node (ref "U$81") (pin "3") (pinfunction "C_3") (pintype "bidirectional"))
      (node (ref "U$82") (pin "1") (pinfunction "A_1") (pintype "bidirectional"))
      (node (ref "U$82") (pin "3") (pinfunction "C_3") (pintype "bidirectional"))
      (node (ref "U$83") (pin "3") (pinfunction "C_3") (pintype "bidirectional"))
      (node (ref "U$84") (pin "1") (pinfunction "A_1") (pintype "bidirectional"))
      (node (ref "U$84") (pin "3") (pinfunction "C_3") (pintype "bidirectional"))
      (node (ref "U$85") (pin "3") (pinfunction "C_3") (pintype "bidirectional"))
      (node (ref "U$86") (pin "1") (pinfunction "A_1") (pintype "bidirectional"))
      (node (ref "U$86") (pin "3") (pinfunction "C_3") (pintype "bidirectional"))
      (node (ref "U$87") (pin "3") (pinfunction "C_3") (pintype "bidirectional"))
      (node (ref "U$88") (pin "1") (pinfunction "A_1") (pintype "bidirectional"))
      (node (ref "U$88") (pin "3") (pinfunction "C_3") (pintype "bidirectional"))
      (node (ref "U$89") (pin "3") (pinfunction "C_3") (pintype "bidirectional"))
      (node (ref "U$90") (pin "1") (pinfunction "A_1") (pintype "bidirectional"))
      (node (ref "U$90") (pin "3") (pinfunction "C_3") (pintype "bidirectional"))
      (node (ref "U$91") (pin "3") (pinfunction "C_3") (pintype "bidirectional"))
      (node (ref "U$92") (pin "1") (pinfunction "A_1") (pintype "bidirectional"))
      (node (ref "U$92") (pin "3") (pinfunction "C_3") (pintype "bidirectional"))
      (node (ref "U$93") (pin "3") (pinfunction "C_3") (pintype "bidirectional"))
      (node (ref "U$94") (pin "1") (pinfunction "A_1") (pintype "bidirectional"))
      (node (ref "U$94") (pin "3") (pinfunction "C_3") (pintype "bidirectional"))
      (node (ref "U$95") (pin "3") (pinfunction "C_3") (pintype "bidirectional"))
      (node (ref "U$96") (pin "1") (pinfunction "A_1") (pintype "bidirectional"))
      (node (ref "U$96") (pin "3") (pinfunction "C_3") (pintype "bidirectional"))
      (node (ref "U$97") (pin "3") (pinfunction "C_3") (pintype "bidirectional"))
      (node (ref "U$98") (pin "1") (pinfunction "A_1") (pintype "bidirectional"))
      (node (ref "U$98") (pin "3") (pinfunction "C_3") (pintype "bidirectional"))
      (node (ref "U$99") (pin "3") (pinfunction "C_3") (pintype "bidirectional"))
      (node (ref "U1") (pin "16") (pinfunction "VCC_16") (pintype "power_in"))
      (node (ref "U2") (pin "16") (pinfunction "VCC_16") (pintype "power_in"))
      (node (ref "U3") (pin "16") (pinfunction "VCC_16") (pintype "power_in"))
      (node (ref "U4") (pin "16") (pinfunction "VCC_16") (pintype "power_in"))
      (node (ref "U5") (pin "16") (pinfunction "VCC_16") (pintype "power_in"))
      (node (ref "U6") (pin "16") (pinfunction "VCC_16") (pintype "power_in"))
      (node (ref "U7") (pin "OUT") (pinfunction "OUT_OUT") (pintype "passive"))
    )
    (net (code "52") (name "5V") (class "Default")
      (node (ref "C7") (pin "1") (pinfunction "1_1") (pintype "passive"))
      (node (ref "J1") (pin "2") (pinfunction "2_2") (pintype "passive"))
      (node (ref "JP1") (pin "1") (pinfunction "1_1") (pintype "passive"))
      (node (ref "U$38") (pin "VIN") (pinfunction "VIN_VIN") (pintype "bidirectional"))
      (node (ref "U$40") (pin "1") (pinfunction "1_1") (pintype "passive"))
      (node (ref "U7") (pin "IN") (pinfunction "IN_IN") (pintype "input"))
    )
    (net (code "53") (name "GND") (class "Default")
      (node (ref "C1") (pin "2") (pinfunction "2_2") (pintype "passive"))
      (node (ref "C2") (pin "2") (pinfunction "2_2") (pintype "passive"))
      (node (ref "C3") (pin "2") (pinfunction "2_2") (pintype "passive"))
      (node (ref "C4") (pin "2") (pinfunction "2_2") (pintype "passive"))
      (node (ref "C5") (pin "2") (pinfunction "2_2") (pintype "passive"))
      (node (ref "C6") (pin "2") (pinfunction "2_2") (pintype "passive"))
      (node (ref "C7") (pin "2") (pinfunction "2_2") (pintype "passive"))
      (node (ref "C8") (pin "-") (pinfunction "-_-") (pintype "passive"))
      (node (ref "J1") (pin "1") (pinfunction "1_1") (pintype "passive"))
      (node (ref "J3") (pin "1") (pinfunction "1_1") (pintype "passive"))
      (node (ref "Q6") (pin "3") (pinfunction "S_3") (pintype "bidirectional"))
      (node (ref "Q7") (pin "3") (pinfunction "S_3") (pintype "bidirectional"))
      (node (ref "R11") (pin "P$1") (pinfunction "1_P$1") (pintype "passive"))
      (node (ref "R12") (pin "P$1") (pinfunction "1_P$1") (pintype "passive"))
      (node (ref "R13") (pin "P$1") (pinfunction "1_P$1") (pintype "passive"))
      (node (ref "R15") (pin "P$1") (pinfunction "1_P$1") (pintype "passive"))
      (node (ref "R2") (pin "P$1") (pinfunction "1_P$1") (pintype "passive"))
      (node (ref "R5") (pin "P$1") (pinfunction "1_P$1") (pintype "passive"))
      (node (ref "R6") (pin "P$1") (pinfunction "1_P$1") (pintype "passive"))
      (node (ref "R7") (pin "P$1") (pinfunction "1_P$1") (pintype "passive"))
      (node (ref "S1") (pin "P1") (pinfunction "P$1_P1") (pintype "bidirectional"))
      (node (ref "S2") (pin "P1") (pinfunction "P$1_P1") (pintype "bidirectional"))
      (node (ref "U$31") (pin "1") (pinfunction "1_1") (pintype "passive"))
      (node (ref "U$38") (pin "GND") (pinfunction "GND_GND") (pintype "bidirectional"))
      (node (ref "U1") (pin "8") (pinfunction "GND_8") (pintype "power_in"))
      (node (ref "U2") (pin "8") (pinfunction "GND_8") (pintype "power_in"))
      (node (ref "U3") (pin "8") (pinfunction "GND_8") (pintype "power_in"))
      (node (ref "U4") (pin "8") (pinfunction "GND_8") (pintype "power_in"))
      (node (ref "U5") (pin "8") (pinfunction "GND_8") (pintype "power_in"))
      (node (ref "U6") (pin "8") (pinfunction "GND_8") (pintype "power_in"))
      (node (ref "U7") (pin "GND") (pinfunction "GND_GND") (pintype "input"))
    )
    (net (code "54") (name "Net-(JP1-Pad2)") (class "Default")
      (node (ref "JP1") (pin "2") (pinfunction "2_2") (pintype "passive"))
      (node (ref "U$38") (pin "USB") (pinfunction "USB_USB") (pintype "bidirectional"))
    )
    (net (code "55") (name "Net-(Q6-D)") (class "Default")
      (node (ref "Q6") (pin "2") (pinfunction "D_2") (pintype "bidirectional"))
      (node (ref "U$34") (pin "P$1") (pinfunction "1_P$1") (pintype "passive"))
      (node (ref "U$35") (pin "P$1") (pinfunction "1_P$1") (pintype "passive"))
    )
    (net (code "56") (name "Net-(Q7-D)") (class "Default")
      (node (ref "Q7") (pin "2") (pinfunction "D_2") (pintype "bidirectional"))
      (node (ref "U$36") (pin "P$1") (pinfunction "1_P$1") (pintype "passive"))
      (node (ref "U$37") (pin "P$1") (pinfunction "1_P$1") (pintype "passive"))
    )
    (net (code "57") (name "Net-(R2-2)") (class "Default")
      (node (ref "R2") (pin "P$2") (pinfunction "2_P$2") (pintype "passive"))
      (node (ref "U$70") (pin "4") (pinfunction "E_4") (pintype "bidirectional"))
      (node (ref "U1") (pin "3") (pinfunction "E_3") (pintype "tri_state"))
    )
    (net (code "58") (name "Net-(R2-3)") (class "Default")
      (node (ref "R2") (pin "P$3") (pinfunction "3_P$3") (pintype "passive"))
      (node (ref "U$71") (pin "4") (pinfunction "E_4") (pintype "bidirectional"))
      (node (ref "U1") (pin "4") (pinfunction "F_4") (pintype "tri_state"))
    )
    (net (code "59") (name "Net-(R2-4)") (class "Default")
      (node (ref "R2") (pin "P$4") (pinfunction "4_P$4") (pintype "passive"))
      (node (ref "U$69") (pin "4") (pinfunction "E_4") (pintype "bidirectional"))
      (node (ref "U1") (pin "6") (pinfunction "H_6") (pintype "tri_state"))
    )
    (net (code "60") (name "Net-(R2-5)") (class "Default")
      (node (ref "R2") (pin "P$5") (pinfunction "5_P$5") (pintype "passive"))
      (node (ref "U$68") (pin "4") (pinfunction "E_4") (pintype "bidirectional"))
      (node (ref "U1") (pin "5") (pinfunction "G_5") (pintype "tri_state"))
    )
    (net (code "61") (name "Net-(R2-6)") (class "Default")
      (node (ref "R2") (pin "P$6") (pinfunction "6_P$6") (pintype "passive"))
      (node (ref "U$73") (pin "4") (pinfunction "E_4") (pintype "bidirectional"))
      (node (ref "U1") (pin "14") (pinfunction "D_14") (pintype "tri_state"))
    )
    (net (code "62") (name "Net-(R2-7)") (class "Default")
      (node (ref "R2") (pin "P$7") (pinfunction "7_P$7") (pintype "passive"))
      (node (ref "U$72") (pin "4") (pinfunction "E_4") (pintype "bidirectional"))
      (node (ref "U1") (pin "13") (pinfunction "C_13") (pintype "tri_state"))
    )
    (net (code "63") (name "Net-(R2-8)") (class "Default")
      (node (ref "R2") (pin "P$8") (pinfunction "8_P$8") (pintype "passive"))
      (node (ref "U$75") (pin "4") (pinfunction "E_4") (pintype "bidirectional"))
      (node (ref "U1") (pin "12") (pinfunction "B_12") (pintype "tri_state"))
    )
    (net (code "64") (name "Net-(R2-9)") (class "Default")
      (node (ref "R2") (pin "P$9") (pinfunction "9_P$9") (pintype "passive"))
      (node (ref "U$74") (pin "4") (pinfunction "E_4") (pintype "bidirectional"))
      (node (ref "U1") (pin "11") (pinfunction "A_11") (pintype "tri_state"))
    )
    (net (code "65") (name "Net-(R5-2)") (class "Default")
      (node (ref "R5") (pin "P$2") (pinfunction "2_P$2") (pintype "passive"))
      (node (ref "U$82") (pin "4") (pinfunction "E_4") (pintype "bidirectional"))
      (node (ref "U2") (pin "11") (pinfunction "A_11") (pintype "tri_state"))
    )
    (net (code "66") (name "Net-(R5-3)") (class "Default")
      (node (ref "R5") (pin "P$3") (pinfunction "3_P$3") (pintype "passive"))
      (node (ref "U$83") (pin "4") (pinfunction "E_4") (pintype "bidirectional"))
      (node (ref "U2") (pin "12") (pinfunction "B_12") (pintype "tri_state"))
    )
    (net (code "67") (name "Net-(R5-4)") (class "Default")
      (node (ref "R5") (pin "P$4") (pinfunction "4_P$4") (pintype "passive"))
      (node (ref "U$80") (pin "4") (pinfunction "E_4") (pintype "bidirectional"))
      (node (ref "U2") (pin "13") (pinfunction "C_13") (pintype "tri_state"))
    )
    (net (code "68") (name "Net-(R5-5)") (class "Default")
      (node (ref "R5") (pin "P$5") (pinfunction "5_P$5") (pintype "passive"))
      (node (ref "U$81") (pin "4") (pinfunction "E_4") (pintype "bidirectional"))
      (node (ref "U2") (pin "14") (pinfunction "D_14") (pintype "tri_state"))
    )
    (net (code "69") (name "Net-(R5-6)") (class "Default")
      (node (ref "R5") (pin "P$6") (pinfunction "6_P$6") (pintype "passive"))
      (node (ref "U$78") (pin "4") (pinfunction "E_4") (pintype "bidirectional"))
      (node (ref "U2") (pin "3") (pinfunction "E_3") (pintype "tri_state"))
    )
    (net (code "70") (name "Net-(R5-7)") (class "Default")
      (node (ref "R5") (pin "P$7") (pinfunction "7_P$7") (pintype "passive"))
      (node (ref "U$79") (pin "4") (pinfunction "E_4") (pintype "bidirectional"))
      (node (ref "U2") (pin "4") (pinfunction "F_4") (pintype "tri_state"))
    )
    (net (code "71") (name "Net-(R5-8)") (class "Default")
      (node (ref "R5") (pin "P$8") (pinfunction "8_P$8") (pintype "passive"))
      (node (ref "U$76") (pin "4") (pinfunction "E_4") (pintype "bidirectional"))
      (node (ref "U2") (pin "5") (pinfunction "G_5") (pintype "tri_state"))
    )
    (net (code "72") (name "Net-(R5-9)") (class "Default")
      (node (ref "R5") (pin "P$9") (pinfunction "9_P$9") (pintype "passive"))
      (node (ref "U$77") (pin "4") (pinfunction "E_4") (pintype "bidirectional"))
      (node (ref "U2") (pin "6") (pinfunction "H_6") (pintype "tri_state"))
    )
    (net (code "73") (name "Net-(R6-2)") (class "Default")
      (node (ref "R6") (pin "P$2") (pinfunction "2_P$2") (pintype "passive"))
      (node (ref "U$91") (pin "4") (pinfunction "E_4") (pintype "bidirectional"))
      (node (ref "U3") (pin "12") (pinfunction "B_12") (pintype "tri_state"))
    )
    (net (code "74") (name "Net-(R6-3)") (class "Default")
      (node (ref "R6") (pin "P$3") (pinfunction "3_P$3") (pintype "passive"))
      (node (ref "U$90") (pin "4") (pinfunction "E_4") (pintype "bidirectional"))
      (node (ref "U3") (pin "11") (pinfunction "A_11") (pintype "tri_state"))
    )
    (net (code "75") (name "Net-(R6-4)") (class "Default")
      (node (ref "R6") (pin "P$4") (pinfunction "4_P$4") (pintype "passive"))
      (node (ref "U$88") (pin "4") (pinfunction "E_4") (pintype "bidirectional"))
      (node (ref "U3") (pin "13") (pinfunction "C_13") (pintype "tri_state"))
    )
    (net (code "76") (name "Net-(R6-5)") (class "Default")
      (node (ref "R6") (pin "P$5") (pinfunction "5_P$5") (pintype "passive"))
      (node (ref "U$89") (pin "4") (pinfunction "E_4") (pintype "bidirectional"))
      (node (ref "U3") (pin "14") (pinfunction "D_14") (pintype "tri_state"))
    )
    (net (code "77") (name "Net-(R6-6)") (class "Default")
      (node (ref "R6") (pin "P$6") (pinfunction "6_P$6") (pintype "passive"))
      (node (ref "U$86") (pin "4") (pinfunction "E_4") (pintype "bidirectional"))
      (node (ref "U3") (pin "3") (pinfunction "E_3") (pintype "tri_state"))
    )
    (net (code "78") (name "Net-(R6-7)") (class "Default")
      (node (ref "R6") (pin "P$7") (pinfunction "7_P$7") (pintype "passive"))
      (node (ref "U$87") (pin "4") (pinfunction "E_4") (pintype "bidirectional"))
      (node (ref "U3") (pin "4") (pinfunction "F_4") (pintype "tri_state"))
    )
    (net (code "79") (name "Net-(R6-8)") (class "Default")
      (node (ref "R6") (pin "P$8") (pinfunction "8_P$8") (pintype "passive"))
      (node (ref "U$84") (pin "4") (pinfunction "E_4") (pintype "bidirectional"))
      (node (ref "U3") (pin "5") (pinfunction "G_5") (pintype "tri_state"))
    )
    (net (code "80") (name "Net-(R6-9)") (class "Default")
      (node (ref "R6") (pin "P$9") (pinfunction "9_P$9") (pintype "passive"))
      (node (ref "U$85") (pin "4") (pinfunction "E_4") (pintype "bidirectional"))
      (node (ref "U3") (pin "6") (pinfunction "H_6") (pintype "tri_state"))
    )
    (net (code "81") (name "Net-(R7-2)") (class "Default")
      (node (ref "R7") (pin "P$2") (pinfunction "2_P$2") (pintype "passive"))
      (node (ref "U$98") (pin "4") (pinfunction "E_4") (pintype "bidirectional"))
      (node (ref "U4") (pin "11") (pinfunction "A_11") (pintype "tri_state"))
    )
    (net (code "82") (name "Net-(R7-3)") (class "Default")
      (node (ref "R7") (pin "P$3") (pinfunction "3_P$3") (pintype "passive"))
      (node (ref "U$99") (pin "4") (pinfunction "E_4") (pintype "bidirectional"))
      (node (ref "U4") (pin "12") (pinfunction "B_12") (pintype "tri_state"))
    )
    (net (code "83") (name "Net-(R7-4)") (class "Default")
      (node (ref "R7") (pin "P$4") (pinfunction "4_P$4") (pintype "passive"))
      (node (ref "U$96") (pin "4") (pinfunction "E_4") (pintype "bidirectional"))
      (node (ref "U4") (pin "13") (pinfunction "C_13") (pintype "tri_state"))
    )
    (net (code "84") (name "Net-(R7-5)") (class "Default")
      (node (ref "R7") (pin "P$5") (pinfunction "5_P$5") (pintype "passive"))
      (node (ref "U$97") (pin "4") (pinfunction "E_4") (pintype "bidirectional"))
      (node (ref "U4") (pin "14") (pinfunction "D_14") (pintype "tri_state"))
    )
    (net (code "85") (name "Net-(R7-6)") (class "Default")
      (node (ref "R7") (pin "P$6") (pinfunction "6_P$6") (pintype "passive"))
      (node (ref "U$94") (pin "4") (pinfunction "E_4") (pintype "bidirectional"))
      (node (ref "U4") (pin "3") (pinfunction "E_3") (pintype "tri_state"))
    )
    (net (code "86") (name "Net-(R7-7)") (class "Default")
      (node (ref "R7") (pin "P$7") (pinfunction "7_P$7") (pintype "passive"))
      (node (ref "U$95") (pin "4") (pinfunction "E_4") (pintype "bidirectional"))
      (node (ref "U4") (pin "4") (pinfunction "F_4") (pintype "tri_state"))
    )
    (net (code "87") (name "Net-(R7-8)") (class "Default")
      (node (ref "R7") (pin "P$8") (pinfunction "8_P$8") (pintype "passive"))
      (node (ref "U$92") (pin "4") (pinfunction "E_4") (pintype "bidirectional"))
      (node (ref "U4") (pin "5") (pinfunction "G_5") (pintype "tri_state"))
    )
    (net (code "88") (name "Net-(R7-9)") (class "Default")
      (node (ref "R7") (pin "P$9") (pinfunction "9_P$9") (pintype "passive"))
      (node (ref "U$93") (pin "4") (pinfunction "E_4") (pintype "bidirectional"))
      (node (ref "U4") (pin "6") (pinfunction "H_6") (pintype "tri_state"))
    )
    (net (code "89") (name "Net-(R11-2)") (class "Default")
      (node (ref "R11") (pin "P$2") (pinfunction "2_P$2") (pintype "passive"))
      (node (ref "U$106") (pin "4") (pinfunction "E_4") (pintype "bidirectional"))
      (node (ref "U5") (pin "11") (pinfunction "A_11") (pintype "tri_state"))
    )
    (net (code "90") (name "Net-(R11-3)") (class "Default")
      (node (ref "R11") (pin "P$3") (pinfunction "3_P$3") (pintype "passive"))
      (node (ref "U$107") (pin "4") (pinfunction "E_4") (pintype "bidirectional"))
      (node (ref "U5") (pin "12") (pinfunction "B_12") (pintype "tri_state"))
    )
    (net (code "91") (name "Net-(R11-4)") (class "Default")
      (node (ref "R11") (pin "P$4") (pinfunction "4_P$4") (pintype "passive"))
      (node (ref "U$104") (pin "4") (pinfunction "E_4") (pintype "bidirectional"))
      (node (ref "U5") (pin "13") (pinfunction "C_13") (pintype "tri_state"))
    )
    (net (code "92") (name "Net-(R11-5)") (class "Default")
      (node (ref "R11") (pin "P$5") (pinfunction "5_P$5") (pintype "passive"))
      (node (ref "U$105") (pin "4") (pinfunction "E_4") (pintype "bidirectional"))
      (node (ref "U5") (pin "14") (pinfunction "D_14") (pintype "tri_state"))
    )
    (net (code "93") (name "Net-(R11-6)") (class "Default")
      (node (ref "R11") (pin "P$6") (pinfunction "6_P$6") (pintype "passive"))
      (node (ref "U$102") (pin "4") (pinfunction "E_4") (pintype "bidirectional"))
      (node (ref "U5") (pin "3") (pinfunction "E_3") (pintype "tri_state"))
    )
    (net (code "94") (name "Net-(R11-7)") (class "Default")
      (node (ref "R11") (pin "P$7") (pinfunction "7_P$7") (pintype "passive"))
      (node (ref "U$103") (pin "4") (pinfunction "E_4") (pintype "bidirectional"))
      (node (ref "U5") (pin "4") (pinfunction "F_4") (pintype "tri_state"))
    )
    (net (code "95") (name "Net-(R11-8)") (class "Default")
      (node (ref "R11") (pin "P$8") (pinfunction "8_P$8") (pintype "passive"))
      (node (ref "U$100") (pin "4") (pinfunction "E_4") (pintype "bidirectional"))
      (node (ref "U5") (pin "5") (pinfunction "G_5") (pintype "tri_state"))
    )
    (net (code "96") (name "Net-(R11-9)") (class "Default")
      (node (ref "R11") (pin "P$9") (pinfunction "9_P$9") (pintype "passive"))
      (node (ref "U$101") (pin "4") (pinfunction "E_4") (pintype "bidirectional"))
      (node (ref "U5") (pin "6") (pinfunction "H_6") (pintype "tri_state"))
    )
    (net (code "97") (name "Net-(R12-2)") (class "Default")
      (node (ref "R12") (pin "P$2") (pinfunction "2_P$2") (pintype "passive"))
      (node (ref "U$115") (pin "4") (pinfunction "E_4") (pintype "bidirectional"))
      (node (ref "U6") (pin "12") (pinfunction "B_12") (pintype "tri_state"))
    )
    (net (code "98") (name "Net-(R12-3)") (class "Default")
      (node (ref "R12") (pin "P$3") (pinfunction "3_P$3") (pintype "passive"))
      (node (ref "U$114") (pin "4") (pinfunction "E_4") (pintype "bidirectional"))
      (node (ref "U6") (pin "11") (pinfunction "A_11") (pintype "tri_state"))
    )
    (net (code "99") (name "Net-(R12-4)") (class "Default")
      (node (ref "R12") (pin "P$4") (pinfunction "4_P$4") (pintype "passive"))
      (node (ref "U$112") (pin "4") (pinfunction "E_4") (pintype "bidirectional"))
      (node (ref "U6") (pin "13") (pinfunction "C_13") (pintype "tri_state"))
    )
    (net (code "100") (name "Net-(R12-5)") (class "Default")
      (node (ref "R12") (pin "P$5") (pinfunction "5_P$5") (pintype "passive"))
      (node (ref "U$113") (pin "4") (pinfunction "E_4") (pintype "bidirectional"))
      (node (ref "U6") (pin "14") (pinfunction "D_14") (pintype "tri_state"))
    )
    (net (code "101") (name "Net-(R12-6)") (class "Default")
      (node (ref "R12") (pin "P$6") (pinfunction "6_P$6") (pintype "passive"))
      (node (ref "U$110") (pin "4") (pinfunction "E_4") (pintype "bidirectional"))
      (node (ref "U6") (pin "3") (pinfunction "E_3") (pintype "tri_state"))
    )
    (net (code "102") (name "Net-(R12-7)") (class "Default")
      (node (ref "R12") (pin "P$7") (pinfunction "7_P$7") (pintype "passive"))
      (node (ref "U$111") (pin "4") (pinfunction "E_4") (pintype "bidirectional"))
      (node (ref "U6") (pin "4") (pinfunction "F_4") (pintype "tri_state"))
    )
    (net (code "103") (name "Net-(R12-8)") (class "Default")
      (node (ref "R12") (pin "P$8") (pinfunction "8_P$8") (pintype "passive"))
      (node (ref "U$108") (pin "4") (pinfunction "E_4") (pintype "bidirectional"))
      (node (ref "U6") (pin "5") (pinfunction "G_5") (pintype "tri_state"))
    )
    (net (code "104") (name "Net-(R12-9)") (class "Default")
      (node (ref "R12") (pin "P$9") (pinfunction "9_P$9") (pintype "passive"))
      (node (ref "U$109") (pin "4") (pinfunction "E_4") (pintype "bidirectional"))
      (node (ref "U6") (pin "6") (pinfunction "H_6") (pintype "tri_state"))
    )
    (net (code "105") (name "Net-(U$68-K)") (class "Default")
      (node (ref "U$68") (pin "2") (pinfunction "K_2") (pintype "bidirectional"))
      (node (ref "U$69") (pin "1") (pinfunction "A_1") (pintype "bidirectional"))
    )
    (net (code "106") (name "Net-(U$70-K)") (class "Default")
      (node (ref "U$70") (pin "2") (pinfunction "K_2") (pintype "bidirectional"))
      (node (ref "U$71") (pin "1") (pinfunction "A_1") (pintype "bidirectional"))
    )
    (net (code "107") (name "Net-(U$72-K)") (class "Default")
      (node (ref "U$72") (pin "2") (pinfunction "K_2") (pintype "bidirectional"))
      (node (ref "U$73") (pin "1") (pinfunction "A_1") (pintype "bidirectional"))
    )
    (net (code "108") (name "Net-(U$74-K)") (class "Default")
      (node (ref "U$74") (pin "2") (pinfunction "K_2") (pintype "bidirectional"))
      (node (ref "U$75") (pin "1") (pinfunction "A_1") (pintype "bidirectional"))
    )
    (net (code "109") (name "Net-(U$76-K)") (class "Default")
      (node (ref "U$76") (pin "2") (pinfunction "K_2") (pintype "bidirectional"))
      (node (ref "U$77") (pin "1") (pinfunction "A_1") (pintype "bidirectional"))
    )
    (net (code "110") (name "Net-(U$78-K)") (class "Default")
      (node (ref "U$78") (pin "2") (pinfunction "K_2") (pintype "bidirectional"))
      (node (ref "U$79") (pin "1") (pinfunction "A_1") (pintype "bidirectional"))
    )
    (net (code "111") (name "Net-(U$80-K)") (class "Default")
      (node (ref "U$80") (pin "2") (pinfunction "K_2") (pintype "bidirectional"))
      (node (ref "U$81") (pin "1") (pinfunction "A_1") (pintype "bidirectional"))
    )
    (net (code "112") (name "Net-(U$82-K)") (class "Default")
      (node (ref "U$82") (pin "2") (pinfunction "K_2") (pintype "bidirectional"))
      (node (ref "U$83") (pin "1") (pinfunction "A_1") (pintype "bidirectional"))
    )
    (net (code "113") (name "Net-(U$84-K)") (class "Default")
      (node (ref "U$84") (pin "2") (pinfunction "K_2") (pintype "bidirectional"))
      (node (ref "U$85") (pin "1") (pinfunction "A_1") (pintype "bidirectional"))
    )
    (net (code "114") (name "Net-(U$86-K)") (class "Default")
      (node (ref "U$86") (pin "2") (pinfunction "K_2") (pintype "bidirectional"))
      (node (ref "U$87") (pin "1") (pinfunction "A_1") (pintype "bidirectional"))
    )
    (net (code "115") (name "Net-(U$88-K)") (class "Default")
      (node (ref "U$88") (pin "2") (pinfunction "K_2") (pintype "bidirectional"))
      (node (ref "U$89") (pin "1") (pinfunction "A_1") (pintype "bidirectional"))
    )
    (net (code "116") (name "Net-(U$90-K)") (class "Default")
      (node (ref "U$90") (pin "2") (pinfunction "K_2") (pintype "bidirectional"))
      (node (ref "U$91") (pin "1") (pinfunction "A_1") (pintype "bidirectional"))
    )
    (net (code "117") (name "Net-(U$92-K)") (class "Default")
      (node (ref "U$92") (pin "2") (pinfunction "K_2") (pintype "bidirectional"))
      (node (ref "U$93") (pin "1") (pinfunction "A_1") (pintype "bidirectional"))
    )
    (net (code "118") (name "Net-(U$94-K)") (class "Default")
      (node (ref "U$94") (pin "2") (pinfunction "K_2") (pintype "bidirectional"))
      (node (ref "U$95") (pin "1") (pinfunction "A_1") (pintype "bidirectional"))
    )
    (net (code "119") (name "Net-(U$96-K)") (class "Default")
      (node (ref "U$96") (pin "2") (pinfunction "K_2") (pintype "bidirectional"))
      (node (ref "U$97") (pin "1") (pinfunction "A_1") (pintype "bidirectional"))
    )
    (net (code "120") (name "Net-(U$98-K)") (class "Default")
      (node (ref "U$98") (pin "2") (pinfunction "K_2") (pintype "bidirectional"))
      (node (ref "U$99") (pin "1") (pinfunction "A_1") (pintype "bidirectional"))
    )
    (net (code "121") (name "Net-(U$100-K)") (class "Default")
      (node (ref "U$100") (pin "2") (pinfunction "K_2") (pintype "bidirectional"))
      (node (ref "U$101") (pin "1") (pinfunction "A_1") (pintype "bidirectional"))
    )
    (net (code "122") (name "Net-(U$102-K)") (class "Default")
      (node (ref "U$102") (pin "2") (pinfunction "K_2") (pintype "bidirectional"))
      (node (ref "U$103") (pin "1") (pinfunction "A_1") (pintype "bidirectional"))
    )
    (net (code "123") (name "Net-(U$104-K)") (class "Default")
      (node (ref "U$104") (pin "2") (pinfunction "K_2") (pintype "bidirectional"))
      (node (ref "U$105") (pin "1") (pinfunction "A_1") (pintype "bidirectional"))
    )
    (net (code "124") (name "Net-(U$106-K)") (class "Default")
      (node (ref "U$106") (pin "2") (pinfunction "K_2") (pintype "bidirectional"))
      (node (ref "U$107") (pin "1") (pinfunction "A_1") (pintype "bidirectional"))
    )
    (net (code "125") (name "Net-(U$108-K)") (class "Default")
      (node (ref "U$108") (pin "2") (pinfunction "K_2") (pintype "bidirectional"))
      (node (ref "U$109") (pin "1") (pinfunction "A_1") (pintype "bidirectional"))
    )
    (net (code "126") (name "Net-(U$110-K)") (class "Default")
      (node (ref "U$110") (pin "2") (pinfunction "K_2") (pintype "bidirectional"))
      (node (ref "U$111") (pin "1") (pinfunction "A_1") (pintype "bidirectional"))
    )
    (net (code "127") (name "Net-(U$112-K)") (class "Default")
      (node (ref "U$112") (pin "2") (pinfunction "K_2") (pintype "bidirectional"))
      (node (ref "U$113") (pin "1") (pinfunction "A_1") (pintype "bidirectional"))
    )
    (net (code "128") (name "Net-(U$114-K)") (class "Default")
      (node (ref "U$114") (pin "2") (pinfunction "K_2") (pintype "bidirectional"))
      (node (ref "U$115") (pin "1") (pinfunction "A_1") (pintype "bidirectional"))
    )
    (net (code "129") (name "unconnected-(U$1-4-Pad1)") (class "Default")
      (node (ref "U$1") (pin "1") (pinfunction "4_1") (pintype "passive"))
    )
    (net (code "130") (name "unconnected-(U$1-Pad6)") (class "Default")
      (node (ref "U$1") (pin "6") (pinfunction "6_6") (pintype "passive"))
    )
    (net (code "131") (name "unconnected-(U$2-4-Pad1)") (class "Default")
      (node (ref "U$2") (pin "1") (pinfunction "4_1") (pintype "passive"))
    )
    (net (code "132") (name "unconnected-(U$2-Pad6)") (class "Default")
      (node (ref "U$2") (pin "6") (pinfunction "6_6") (pintype "passive"))
    )
    (net (code "133") (name "unconnected-(U$3-4-Pad1)") (class "Default")
      (node (ref "U$3") (pin "1") (pinfunction "4_1") (pintype "passive"))
    )
    (net (code "134") (name "unconnected-(U$3-Pad6)") (class "Default")
      (node (ref "U$3") (pin "6") (pinfunction "6_6") (pintype "passive"))
    )
    (net (code "135") (name "unconnected-(U$4-4-Pad1)") (class "Default")
      (node (ref "U$4") (pin "1") (pinfunction "4_1") (pintype "passive"))
    )
    (net (code "136") (name "unconnected-(U$4-Pad6)") (class "Default")
      (node (ref "U$4") (pin "6") (pinfunction "6_6") (pintype "passive"))
    )
    (net (code "137") (name "unconnected-(U$5-4-Pad1)") (class "Default")
      (node (ref "U$5") (pin "1") (pinfunction "4_1") (pintype "passive"))
    )
    (net (code "138") (name "unconnected-(U$5-Pad6)") (class "Default")
      (node (ref "U$5") (pin "6") (pinfunction "6_6") (pintype "passive"))
    )
    (net (code "139") (name "unconnected-(U$6-4-Pad1)") (class "Default")
      (node (ref "U$6") (pin "1") (pinfunction "4_1") (pintype "passive"))
    )
    (net (code "140") (name "unconnected-(U$6-Pad6)") (class "Default")
      (node (ref "U$6") (pin "6") (pinfunction "6_6") (pintype "passive"))
    )
    (net (code "141") (name "unconnected-(U$7-4-Pad1)") (class "Default")
      (node (ref "U$7") (pin "1") (pinfunction "4_1") (pintype "passive"))
    )
    (net (code "142") (name "unconnected-(U$7-Pad6)") (class "Default")
      (node (ref "U$7") (pin "6") (pinfunction "6_6") (pintype "passive"))
    )
    (net (code "143") (name "unconnected-(U$8-4-Pad1)") (class "Default")
      (node (ref "U$8") (pin "1") (pinfunction "4_1") (pintype "passive"))
    )
    (net (code "144") (name "unconnected-(U$8-Pad6)") (class "Default")
      (node (ref "U$8") (pin "6") (pinfunction "6_6") (pintype "passive"))
    )
    (net (code "145") (name "unconnected-(U$9-4-Pad1)") (class "Default")
      (node (ref "U$9") (pin "1") (pinfunction "4_1") (pintype "passive"))
    )
    (net (code "146") (name "unconnected-(U$9-Pad6)") (class "Default")
      (node (ref "U$9") (pin "6") (pinfunction "6_6") (pintype "passive"))
    )
    (net (code "147") (name "unconnected-(U$10-4-Pad1)") (class "Default")
      (node (ref "U$10") (pin "1") (pinfunction "4_1") (pintype "passive"))
    )
    (net (code "148") (name "unconnected-(U$10-Pad6)") (class "Default")
      (node (ref "U$10") (pin "6") (pinfunction "6_6") (pintype "passive"))
    )
    (net (code "149") (name "unconnected-(U$11-4-Pad1)") (class "Default")
      (node (ref "U$11") (pin "1") (pinfunction "4_1") (pintype "passive"))
    )
    (net (code "150") (name "unconnected-(U$11-Pad6)") (class "Default")
      (node (ref "U$11") (pin "6") (pinfunction "6_6") (pintype "passive"))
    )
    (net (code "151") (name "unconnected-(U$12-4-Pad1)") (class "Default")
      (node (ref "U$12") (pin "1") (pinfunction "4_1") (pintype "passive"))
    )
    (net (code "152") (name "unconnected-(U$12-Pad6)") (class "Default")
      (node (ref "U$12") (pin "6") (pinfunction "6_6") (pintype "passive"))
    )
    (net (code "153") (name "unconnected-(U$13-4-Pad1)") (class "Default")
      (node (ref "U$13") (pin "1") (pinfunction "4_1") (pintype "passive"))
    )
    (net (code "154") (name "unconnected-(U$13-Pad6)") (class "Default")
      (node (ref "U$13") (pin "6") (pinfunction "6_6") (pintype "passive"))
    )
    (net (code "155") (name "unconnected-(U$14-4-Pad1)") (class "Default")
      (node (ref "U$14") (pin "1") (pinfunction "4_1") (pintype "passive"))
    )
    (net (code "156") (name "unconnected-(U$14-Pad6)") (class "Default")
      (node (ref "U$14") (pin "6") (pinfunction "6_6") (pintype "passive"))
    )
    (net (code "157") (name "unconnected-(U$15-4-Pad1)") (class "Default")
      (node (ref "U$15") (pin "1") (pinfunction "4_1") (pintype "passive"))
    )
    (net (code "158") (name "unconnected-(U$15-Pad6)") (class "Default")
      (node (ref "U$15") (pin "6") (pinfunction "6_6") (pintype "passive"))
    )
    (net (code "159") (name "unconnected-(U$16-4-Pad1)") (class "Default")
      (node (ref "U$16") (pin "1") (pinfunction "4_1") (pintype "passive"))
    )
    (net (code "160") (name "unconnected-(U$16-Pad6)") (class "Default")
      (node (ref "U$16") (pin "6") (pinfunction "6_6") (pintype "passive"))
    )
    (net (code "161") (name "unconnected-(U$17-4-Pad1)") (class "Default")
      (node (ref "U$17") (pin "1") (pinfunction "4_1") (pintype "passive"))
    )
    (net (code "162") (name "unconnected-(U$17-Pad6)") (class "Default")
      (node (ref "U$17") (pin "6") (pinfunction "6_6") (pintype "passive"))
    )
    (net (code "163") (name "unconnected-(U$18-4-Pad1)") (class "Default")
      (node (ref "U$18") (pin "1") (pinfunction "4_1") (pintype "passive"))
    )
    (net (code "164") (name "unconnected-(U$18-Pad6)") (class "Default")
      (node (ref "U$18") (pin "6") (pinfunction "6_6") (pintype "passive"))
    )
    (net (code "165") (name "unconnected-(U$19-4-Pad1)") (class "Default")
      (node (ref "U$19") (pin "1") (pinfunction "4_1") (pintype "passive"))
    )
    (net (code "166") (name "unconnected-(U$19-Pad6)") (class "Default")
      (node (ref "U$19") (pin "6") (pinfunction "6_6") (pintype "passive"))
    )
    (net (code "167") (name "unconnected-(U$20-4-Pad1)") (class "Default")
      (node (ref "U$20") (pin "1") (pinfunction "4_1") (pintype "passive"))
    )
    (net (code "168") (name "unconnected-(U$20-Pad6)") (class "Default")
      (node (ref "U$20") (pin "6") (pinfunction "6_6") (pintype "passive"))
    )
    (net (code "169") (name "unconnected-(U$21-4-Pad1)") (class "Default")
      (node (ref "U$21") (pin "1") (pinfunction "4_1") (pintype "passive"))
    )
    (net (code "170") (name "unconnected-(U$21-Pad6)") (class "Default")
      (node (ref "U$21") (pin "6") (pinfunction "6_6") (pintype "passive"))
    )
    (net (code "171") (name "unconnected-(U$22-4-Pad1)") (class "Default")
      (node (ref "U$22") (pin "1") (pinfunction "4_1") (pintype "passive"))
    )
    (net (code "172") (name "unconnected-(U$22-Pad6)") (class "Default")
      (node (ref "U$22") (pin "6") (pinfunction "6_6") (pintype "passive"))
    )
    (net (code "173") (name "unconnected-(U$23-4-Pad1)") (class "Default")
      (node (ref "U$23") (pin "1") (pinfunction "4_1") (pintype "passive"))
    )
    (net (code "174") (name "unconnected-(U$23-Pad6)") (class "Default")
      (node (ref "U$23") (pin "6") (pinfunction "6_6") (pintype "passive"))
    )
    (net (code "175") (name "unconnected-(U$24-4-Pad1)") (class "Default")
      (node (ref "U$24") (pin "1") (pinfunction "4_1") (pintype "passive"))
    )
    (net (code "176") (name "unconnected-(U$24-Pad6)") (class "Default")
      (node (ref "U$24") (pin "6") (pinfunction "6_6") (pintype "passive"))
    )
    (net (code "177") (name "unconnected-(U$25-4-Pad1)") (class "Default")
      (node (ref "U$25") (pin "1") (pinfunction "4_1") (pintype "passive"))
    )
    (net (code "178") (name "unconnected-(U$25-Pad6)") (class "Default")
      (node (ref "U$25") (pin "6") (pinfunction "6_6") (pintype "passive"))
    )
    (net (code "179") (name "unconnected-(U$26-4-Pad1)") (class "Default")
      (node (ref "U$26") (pin "1") (pinfunction "4_1") (pintype "passive"))
    )
    (net (code "180") (name "unconnected-(U$26-Pad6)") (class "Default")
      (node (ref "U$26") (pin "6") (pinfunction "6_6") (pintype "passive"))
    )
    (net (code "181") (name "unconnected-(U$27-4-Pad1)") (class "Default")
      (node (ref "U$27") (pin "1") (pinfunction "4_1") (pintype "passive"))
    )
    (net (code "182") (name "unconnected-(U$27-Pad6)") (class "Default")
      (node (ref "U$27") (pin "6") (pinfunction "6_6") (pintype "passive"))
    )
    (net (code "183") (name "unconnected-(U$28-4-Pad1)") (class "Default")
      (node (ref "U$28") (pin "1") (pinfunction "4_1") (pintype "passive"))
    )
    (net (code "184") (name "unconnected-(U$28-Pad6)") (class "Default")
      (node (ref "U$28") (pin "6") (pinfunction "6_6") (pintype "passive"))
    )
    (net (code "185") (name "unconnected-(U$29-4-Pad1)") (class "Default")
      (node (ref "U$29") (pin "1") (pinfunction "4_1") (pintype "passive"))
    )
    (net (code "186") (name "unconnected-(U$29-Pad6)") (class "Default")
      (node (ref "U$29") (pin "6") (pinfunction "6_6") (pintype "passive"))
    )
    (net (code "187") (name "unconnected-(U$30-4-Pad1)") (class "Default")
      (node (ref "U$30") (pin "1") (pinfunction "4_1") (pintype "passive"))
    )
    (net (code "188") (name "unconnected-(U$30-Pad6)") (class "Default")
      (node (ref "U$30") (pin "6") (pinfunction "6_6") (pintype "passive"))
    )
    (net (code "189") (name "unconnected-(U$34-10-PadP$10)") (class "Default")
      (node (ref "U$34") (pin "P$10") (pinfunction "10_P$10") (pintype "passive"))
    )
    (net (code "190") (name "unconnected-(U$35-6-PadP$6)") (class "Default")
      (node (ref "U$35") (pin "P$6") (pinfunction "6_P$6") (pintype "passive"))
    )
    (net (code "191") (name "unconnected-(U$35-7-PadP$7)") (class "Default")
      (node (ref "U$35") (pin "P$7") (pinfunction "7_P$7") (pintype "passive"))
    )
    (net (code "192") (name "unconnected-(U$35-8-PadP$8)") (class "Default")
      (node (ref "U$35") (pin "P$8") (pinfunction "8_P$8") (pintype "passive"))
    )
    (net (code "193") (name "unconnected-(U$35-9-PadP$9)") (class "Default")
      (node (ref "U$35") (pin "P$9") (pinfunction "9_P$9") (pintype "passive"))
    )
    (net (code "194") (name "unconnected-(U$35-10-PadP$10)") (class "Default")
      (node (ref "U$35") (pin "P$10") (pinfunction "10_P$10") (pintype "passive"))
    )
    (net (code "195") (name "unconnected-(U$36-10-PadP$10)") (class "Default")
      (node (ref "U$36") (pin "P$10") (pinfunction "10_P$10") (pintype "passive"))
    )
    (net (code "196") (name "unconnected-(U$37-2-PadP$2)") (class "Default")
      (node (ref "U$37") (pin "P$2") (pinfunction "2_P$2") (pintype "passive"))
    )
    (net (code "197") (name "unconnected-(U$37-3-PadP$3)") (class "Default")
      (node (ref "U$37") (pin "P$3") (pinfunction "3_P$3") (pintype "passive"))
    )
    (net (code "198") (name "unconnected-(U$37-4-PadP$4)") (class "Default")
      (node (ref "U$37") (pin "P$4") (pinfunction "4_P$4") (pintype "passive"))
    )
    (net (code "199") (name "unconnected-(U$37-5-PadP$5)") (class "Default")
      (node (ref "U$37") (pin "P$5") (pinfunction "5_P$5") (pintype "passive"))
    )
    (net (code "200") (name "unconnected-(U$37-10-PadP$10)") (class "Default")
      (node (ref "U$37") (pin "P$10") (pinfunction "10_P$10") (pintype "passive"))
    )
    (net (code "201") (name "unconnected-(U$38-D3-Pad3)") (class "Default")
      (node (ref "U$38") (pin "3") (pinfunction "D3_3") (pintype "bidirectional"))
    )
    (net (code "202") (name "unconnected-(U$38-Pad3V)") (class "Default")
      (node (ref "U$38") (pin "3V") (pinfunction "3V_3V") (pintype "bidirectional"))
    )
    (net (code "203") (name "unconnected-(U$38-PadAREF)") (class "Default")
      (node (ref "U$38") (pin "AREF") (pinfunction "AREF_AREF") (pintype "bidirectional"))
    )
    (net (code "204") (name "unconnected-(U$38-PadEN)") (class "Default")
      (node (ref "U$38") (pin "EN") (pinfunction "EN_EN") (pintype "bidirectional"))
    )
    (net (code "205") (name "unconnected-(U$38-PadRES)") (class "Default")
      (node (ref "U$38") (pin "RES") (pinfunction "RES_RES") (pintype "bidirectional"))
    )
    (net (code "206") (name "unconnected-(U$38-PadSWCLK)") (class "Default")
      (node (ref "U$38") (pin "SWCLK") (pinfunction "SWCLK_SWCLK") (pintype "bidirectional"))
    )
    (net (code "207") (name "unconnected-(U$38-PadSWDI0)") (class "Default")
      (node (ref "U$38") (pin "SWDI0") (pinfunction "SWDI0_SWDI0") (pintype "bidirectional"))
    )
    (net (code "208") (name "unconnected-(U$38-PadVHI)") (class "Default")
      (node (ref "U$38") (pin "VHI") (pinfunction "VHI_VHI") (pintype "bidirectional"))
    )
    (net (code "209") (name "unconnected-(U$59-4-Pad1)") (class "Default")
      (node (ref "U$59") (pin "1") (pinfunction "4_1") (pintype "passive"))
    )
    (net (code "210") (name "unconnected-(U$59-Pad6)") (class "Default")
      (node (ref "U$59") (pin "6") (pinfunction "6_6") (pintype "passive"))
    )
    (net (code "211") (name "unconnected-(U$60-Pad1)") (class "Default")
      (node (ref "U$60") (pin "1") (pinfunction "1_1") (pintype "passive"))
    )
    (net (code "212") (name "unconnected-(U$61-Pad1)") (class "Default")
      (node (ref "U$61") (pin "1") (pinfunction "1_1") (pintype "passive"))
    )
    (net (code "213") (name "unconnected-(U1-SER-Pad10)") (class "Default")
      (node (ref "U1") (pin "10") (pinfunction "SER_10") (pintype "input"))
    )
    (net (code "214") (name "unconnected-(U1-~{QH}-Pad7)") (class "Default")
      (node (ref "U1") (pin "7") (pinfunction "~{QH}_7") (pintype "input"))
    )
    (net (code "215") (name "unconnected-(U2-~{QH}-Pad7)") (class "Default")
      (node (ref "U2") (pin "7") (pinfunction "~{QH}_7") (pintype "input"))
    )
    (net (code "216") (name "unconnected-(U3-~{QH}-Pad7)") (class "Default")
      (node (ref "U3") (pin "7") (pinfunction "~{QH}_7") (pintype "input"))
    )
    (net (code "217") (name "unconnected-(U4-SER-Pad10)") (class "Default")
      (node (ref "U4") (pin "10") (pinfunction "SER_10") (pintype "input"))
    )
    (net (code "218") (name "unconnected-(U4-~{QH}-Pad7)") (class "Default")
      (node (ref "U4") (pin "7") (pinfunction "~{QH}_7") (pintype "input"))
    )
    (net (code "219") (name "unconnected-(U5-~{QH}-Pad7)") (class "Default")
      (node (ref "U5") (pin "7") (pinfunction "~{QH}_7") (pintype "input"))
    )
    (net (code "220") (name "unconnected-(U6-~{QH}-Pad7)") (class "Default")
      (node (ref "U6") (pin "7") (pinfunction "~{QH}_7") (pintype "input"))
    )
  )
)
